# CNC_KONTROL_STM32BIT.net
KiCad netlist of a schematic drawn in EAGLE
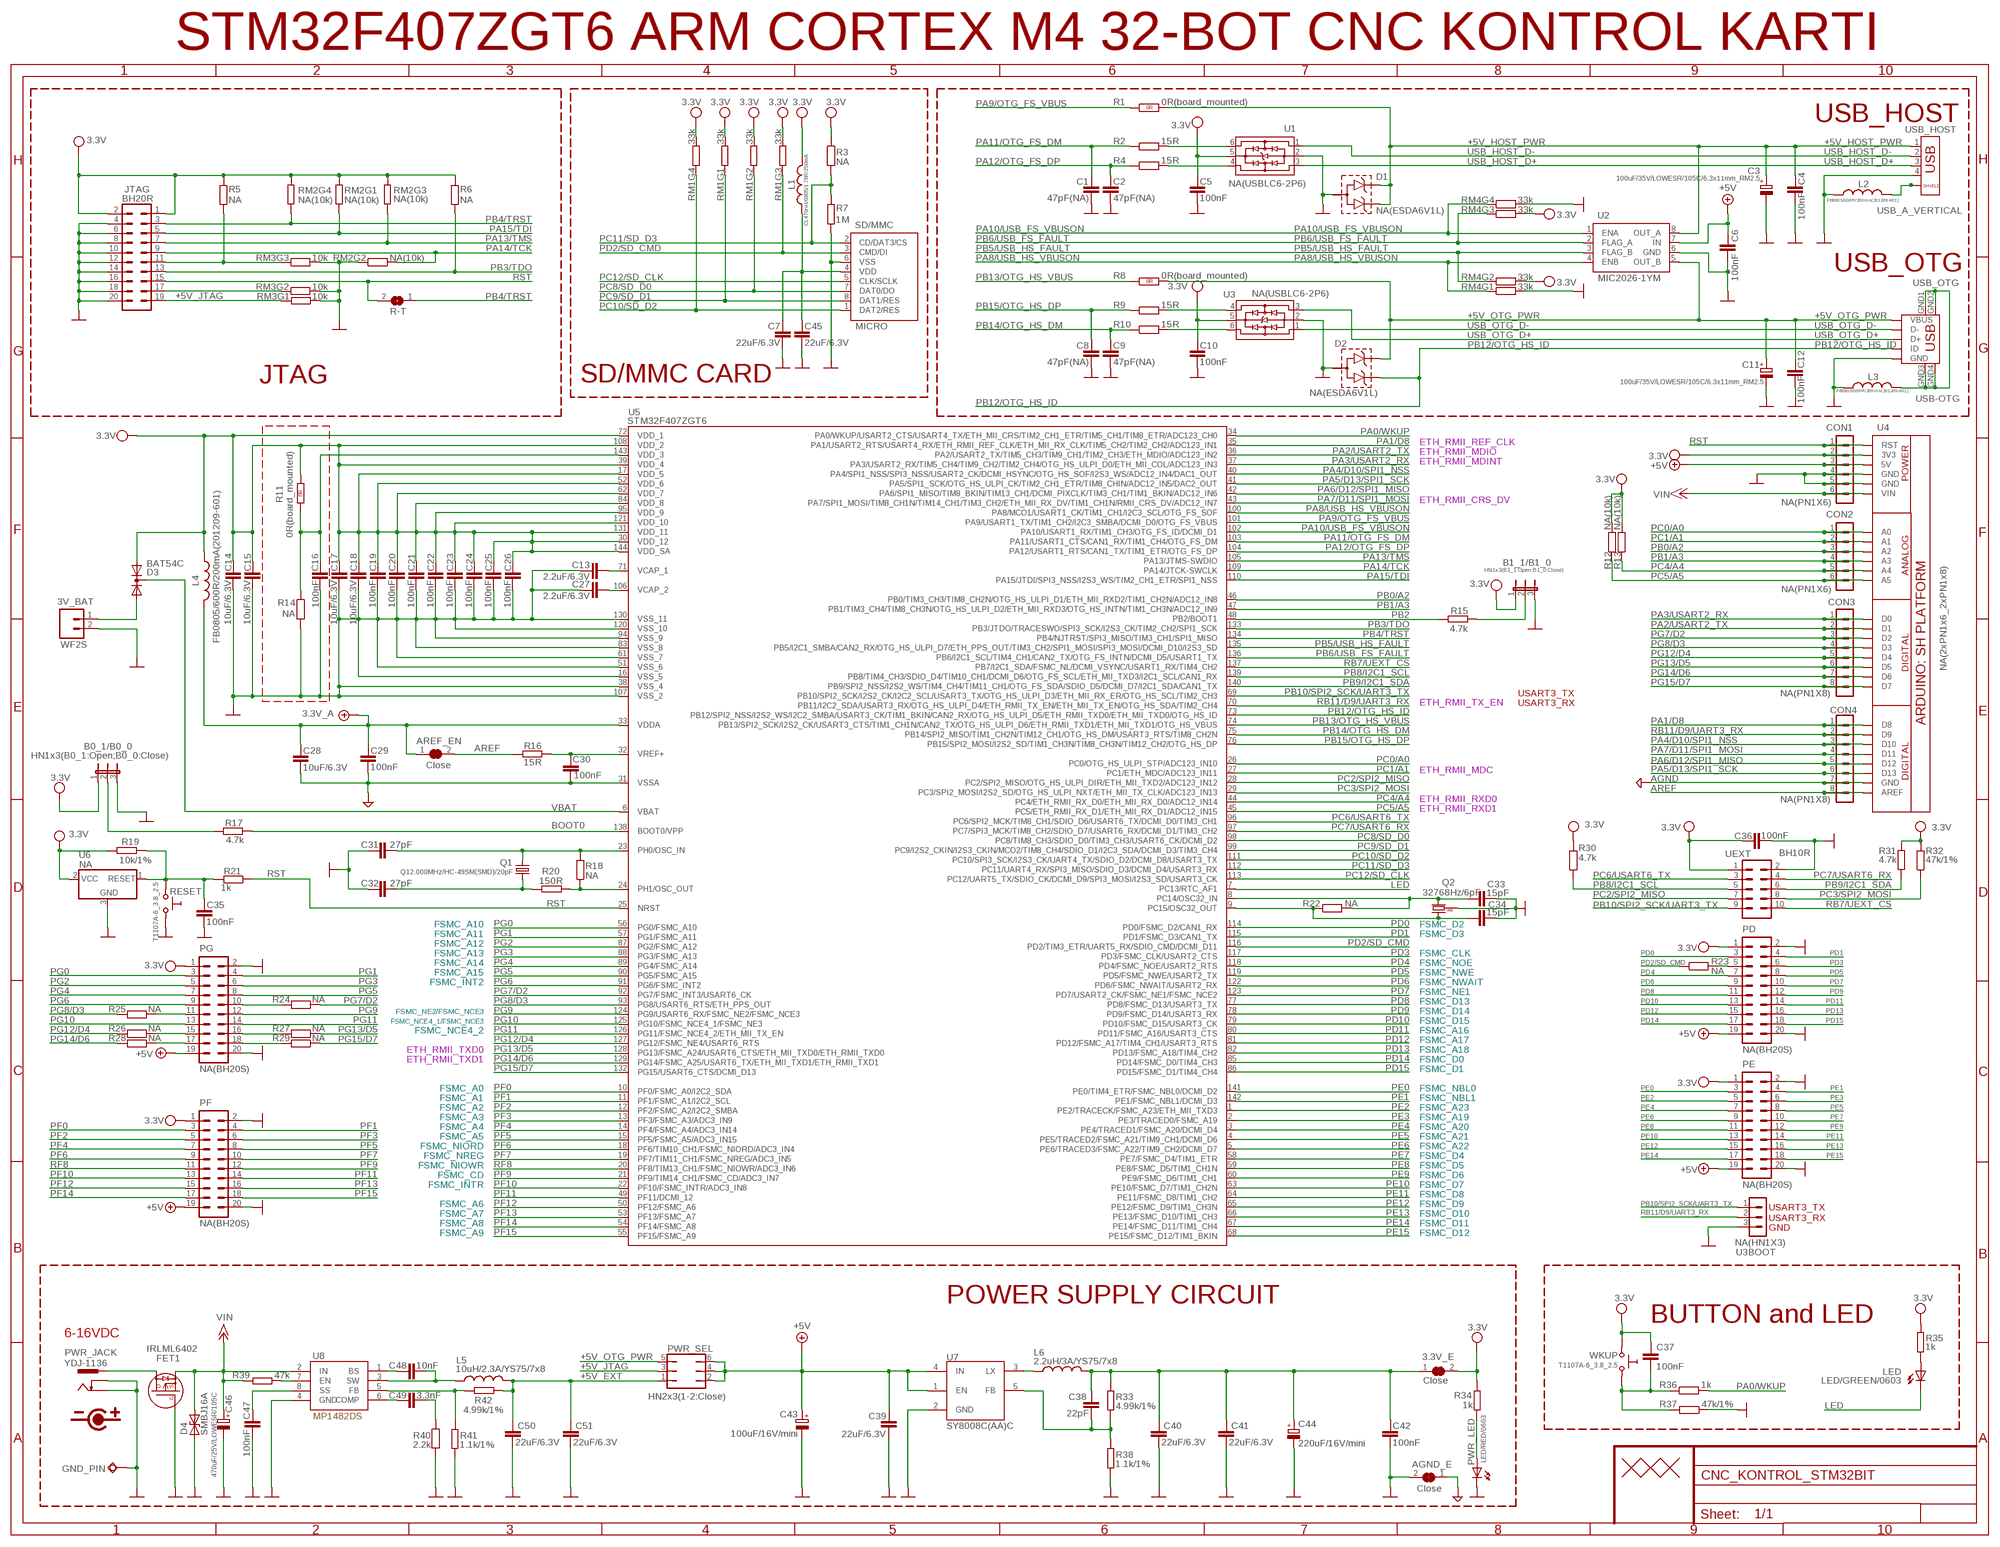
[diagram p0: schematic, sheet 1]

(export (version "E")
  (design (tool "Eeschema 10.0.6"))
  (components
    (comp (ref "3.3V_E")
      (value "Close")
      (footprint "eagle-import:SJ_1_SMALLER_CLOSE")
      (libsource (lib "eagle-import") (part "SJSJ_1_SMALLER_CLOSE"))
    )
    (comp (ref "3V_BAT")
      (value "WF2S")
      (footprint "eagle-import:CON2.54MM-2-0")
      (libsource (lib "eagle-import") (part "CON2PV2-2.54MM"))
    )
    (comp (ref "AGND_E")
      (value "Close")
      (footprint "eagle-import:SJ_1_SMALLER_CLOSE")
      (libsource (lib "eagle-import") (part "SJSJ_1_SMALLER_CLOSE"))
    )
    (comp (ref "AREF_EN")
      (value "Close")
      (footprint "eagle-import:SJ_1_SMALLER_CLOSE")
      (libsource (lib "eagle-import") (part "SJSJ_1_SMALLER_CLOSE"))
    )
    (comp (ref "B0_1/B0_0")
      (value "HN1x3(B0_1:Open;B0_0:Close)")
      (footprint "eagle-import:JP2")
      (libsource (lib "eagle-import") (part "JP2E"))
    )
    (comp (ref "B1_1/B1_0")
      (value "HN1x3(B1_1:Open;B1_0:Close)")
      (footprint "eagle-import:JP2")
      (libsource (lib "eagle-import") (part "JP2E"))
    )
    (comp (ref "C1")
      (value "47pF(NA)")
      (footprint "eagle-import:C0603_DWS")
      (libsource (lib "eagle-import") (part "C-EUC0603_DWS"))
    )
    (comp (ref "C2")
      (value "47pF(NA)")
      (footprint "eagle-import:C0603_DWS")
      (libsource (lib "eagle-import") (part "C-EUC0603_DWS"))
    )
    (comp (ref "C3")
      (value "100uF/35V/LOWESR/105C/6.3x11mm_RM2.5")
      (footprint "eagle-import:E2,5-6,3")
      (libsource (lib "eagle-import") (part "CPOL-EUE2.5-6.3"))
    )
    (comp (ref "C4")
      (value "100nF")
      (footprint "eagle-import:C0603_DWS")
      (libsource (lib "eagle-import") (part "C-EUC0603_DWS"))
    )
    (comp (ref "C5")
      (value "100nF")
      (footprint "eagle-import:C0603_DWS")
      (libsource (lib "eagle-import") (part "C-EUC0603_DWS"))
    )
    (comp (ref "C6")
      (value "100nF")
      (footprint "eagle-import:C0603_DWS")
      (libsource (lib "eagle-import") (part "C-EUC0603_DWS"))
    )
    (comp (ref "C7")
      (value "22uF/6.3V")
      (footprint "eagle-import:C0603_DWS")
      (libsource (lib "eagle-import") (part "C-EUC0603_DWS"))
    )
    (comp (ref "C8")
      (value "47pF(NA)")
      (footprint "eagle-import:C0603_DWS")
      (libsource (lib "eagle-import") (part "C-EUC0603_DWS"))
    )
    (comp (ref "C9")
      (value "47pF(NA)")
      (footprint "eagle-import:C0603_DWS")
      (libsource (lib "eagle-import") (part "C-EUC0603_DWS"))
    )
    (comp (ref "C10")
      (value "100nF")
      (footprint "eagle-import:C0603_DWS")
      (libsource (lib "eagle-import") (part "C-EUC0603_DWS"))
    )
    (comp (ref "C11")
      (value "100uF/35V/LOWESR/105C/6.3x11mm_RM2.5")
      (footprint "eagle-import:E2,5-6,3")
      (libsource (lib "eagle-import") (part "CPOL-EUE2.5-6.3"))
    )
    (comp (ref "C12")
      (value "100nF")
      (footprint "eagle-import:C0603_DWS")
      (libsource (lib "eagle-import") (part "C-EUC0603_DWS"))
    )
    (comp (ref "C13")
      (value "2.2uF/6.3V")
      (footprint "eagle-import:C0603_DWS")
      (libsource (lib "eagle-import") (part "C-EUC0603_DWS"))
    )
    (comp (ref "C14")
      (value "10uF/6.3V")
      (footprint "eagle-import:C0603_DWS")
      (libsource (lib "eagle-import") (part "C-EUC0603_DWS"))
    )
    (comp (ref "C15")
      (value "10uF/6.3V")
      (footprint "eagle-import:C0603_DWS")
      (libsource (lib "eagle-import") (part "C-EUC0603_DWS"))
    )
    (comp (ref "C16")
      (value "100nF")
      (footprint "eagle-import:C0603_DWS")
      (libsource (lib "eagle-import") (part "C-EUC0603_DWS"))
    )
    (comp (ref "C17")
      (value "10uF/6.3V")
      (footprint "eagle-import:C0603_DWS")
      (libsource (lib "eagle-import") (part "C-EUC0603_DWS"))
    )
    (comp (ref "C18")
      (value "10uF/6.3V")
      (footprint "eagle-import:C0603_DWS")
      (libsource (lib "eagle-import") (part "C-EUC0603_DWS"))
    )
    (comp (ref "C19")
      (value "100nF")
      (footprint "eagle-import:C0603_DWS")
      (libsource (lib "eagle-import") (part "C-EUC0603_DWS"))
    )
    (comp (ref "C20")
      (value "100nF")
      (footprint "eagle-import:C0603_DWS")
      (libsource (lib "eagle-import") (part "C-EUC0603_DWS"))
    )
    (comp (ref "C21")
      (value "100nF")
      (footprint "eagle-import:C0603_DWS")
      (libsource (lib "eagle-import") (part "C-EUC0603_DWS"))
    )
    (comp (ref "C22")
      (value "100nF")
      (footprint "eagle-import:C0603_DWS")
      (libsource (lib "eagle-import") (part "C-EUC0603_DWS"))
    )
    (comp (ref "C23")
      (value "100nF")
      (footprint "eagle-import:C0603_DWS")
      (libsource (lib "eagle-import") (part "C-EUC0603_DWS"))
    )
    (comp (ref "C24")
      (value "100nF")
      (footprint "eagle-import:C0603_DWS")
      (libsource (lib "eagle-import") (part "C-EUC0603_DWS"))
    )
    (comp (ref "C25")
      (value "100nF")
      (footprint "eagle-import:C0603_DWS")
      (libsource (lib "eagle-import") (part "C-EUC0603_DWS"))
    )
    (comp (ref "C26")
      (value "100nF")
      (footprint "eagle-import:C0603_DWS")
      (libsource (lib "eagle-import") (part "C-EUC0603_DWS"))
    )
    (comp (ref "C27")
      (value "2.2uF/6.3V")
      (footprint "eagle-import:C0603_DWS")
      (libsource (lib "eagle-import") (part "C-EUC0603_DWS"))
    )
    (comp (ref "C28")
      (value "10uF/6.3V")
      (footprint "eagle-import:C0603_DWS")
      (libsource (lib "eagle-import") (part "C-EUC0603_DWS"))
    )
    (comp (ref "C29")
      (value "100nF")
      (footprint "eagle-import:C0603_DWS")
      (libsource (lib "eagle-import") (part "C-EUC0603_DWS"))
    )
    (comp (ref "C30")
      (value "100nF")
      (footprint "eagle-import:C0603_DWS")
      (libsource (lib "eagle-import") (part "C-EUC0603_DWS"))
    )
    (comp (ref "C31")
      (value "27pF")
      (footprint "eagle-import:C0603_DWS")
      (libsource (lib "eagle-import") (part "C-EUC0603_DWS"))
    )
    (comp (ref "C32")
      (value "27pF")
      (footprint "eagle-import:C0603_DWS")
      (libsource (lib "eagle-import") (part "C-EUC0603_DWS"))
    )
    (comp (ref "C33")
      (value "15pF")
      (footprint "eagle-import:C0603_DWS")
      (libsource (lib "eagle-import") (part "C-EUC0603_DWS"))
    )
    (comp (ref "C34")
      (value "15pF")
      (footprint "eagle-import:C0603_DWS")
      (libsource (lib "eagle-import") (part "C-EUC0603_DWS"))
    )
    (comp (ref "C35")
      (value "100nF")
      (footprint "eagle-import:C0603_DWS")
      (libsource (lib "eagle-import") (part "C-EUC0603_DWS"))
    )
    (comp (ref "C36")
      (value "100nF")
      (footprint "eagle-import:C0603_DWS")
      (libsource (lib "eagle-import") (part "C-EUC0603_DWS"))
    )
    (comp (ref "C37")
      (value "100nF")
      (footprint "eagle-import:C0603_DWS")
      (libsource (lib "eagle-import") (part "C-EUC0603_DWS"))
    )
    (comp (ref "C38")
      (value "22pF")
      (footprint "eagle-import:C0603_DWS")
      (libsource (lib "eagle-import") (part "C-EUC0603_DWS"))
    )
    (comp (ref "C39")
      (value "22uF/6.3V")
      (footprint "eagle-import:C0603_DWS")
      (libsource (lib "eagle-import") (part "C-EUC0603_DWS"))
    )
    (comp (ref "C40")
      (value "22uF/6.3V")
      (footprint "eagle-import:C0603_DWS")
      (libsource (lib "eagle-import") (part "C-EUC0603_DWS"))
    )
    (comp (ref "C41")
      (value "22uF/6.3V")
      (footprint "eagle-import:C0603_DWS")
      (libsource (lib "eagle-import") (part "C-EUC0603_DWS"))
    )
    (comp (ref "C42")
      (value "100nF")
      (footprint "eagle-import:C0603_DWS")
      (libsource (lib "eagle-import") (part "C-EUC0603_DWS"))
    )
    (comp (ref "C43")
      (value "100uF/16V/mini")
      (footprint "eagle-import:E2,5-6")
      (libsource (lib "eagle-import") (part "CPOL-EUE2.5-6"))
    )
    (comp (ref "C44")
      (value "220uF/16V/mini")
      (footprint "eagle-import:E3,5-8")
      (libsource (lib "eagle-import") (part "CPOL-EUE3.5-8"))
    )
    (comp (ref "C45")
      (value "22uF/6.3V")
      (footprint "eagle-import:C0603_DWS")
      (libsource (lib "eagle-import") (part "C-EUC0603_DWS"))
    )
    (comp (ref "C46")
      (value "470uF/25V/LOWESR/105C")
      (footprint "eagle-import:E5-10,5")
      (libsource (lib "eagle-import") (part "CPOL-EUE5-10.5"))
    )
    (comp (ref "C47")
      (value "100nF")
      (footprint "eagle-import:C0603_DWS")
      (libsource (lib "eagle-import") (part "C-EUC0603_DWS"))
    )
    (comp (ref "C48")
      (value "10nF")
      (footprint "eagle-import:C0603_DWS")
      (libsource (lib "eagle-import") (part "C-EUC0603_DWS"))
    )
    (comp (ref "C49")
      (value "3.3nF")
      (footprint "eagle-import:C0603_DWS")
      (libsource (lib "eagle-import") (part "C-EUC0603_DWS"))
    )
    (comp (ref "C50")
      (value "22uF/6.3V")
      (footprint "eagle-import:C0603_DWS")
      (libsource (lib "eagle-import") (part "C-EUC0603_DWS"))
    )
    (comp (ref "C51")
      (value "22uF/6.3V")
      (footprint "eagle-import:C0603_DWS")
      (libsource (lib "eagle-import") (part "C-EUC0603_DWS"))
    )
    (comp (ref "CON1")
      (value "NA(PN1X6)")
      (footprint "eagle-import:PN1X6")
      (libsource (lib "eagle-import") (part "CON6PN1X6"))
    )
    (comp (ref "CON2")
      (value "NA(PN1X6)")
      (footprint "eagle-import:PN1X6")
      (libsource (lib "eagle-import") (part "CON6PN1X6"))
    )
    (comp (ref "CON3")
      (value "NA(PN1X8)")
      (footprint "eagle-import:PN1X8")
      (libsource (lib "eagle-import") (part "CON8PN1X8"))
    )
    (comp (ref "CON4")
      (value "NA(PN1X8)")
      (footprint "eagle-import:PN1X8")
      (libsource (lib "eagle-import") (part "CON8PN1X8"))
    )
    (comp (ref "D1")
      (value "NA(ESDA6V1L)")
      (footprint "eagle-import:SOT-23")
      (libsource (lib "eagle-import") (part "MMBZ5V6ALT1"))
    )
    (comp (ref "D2")
      (value "NA(ESDA6V1L)")
      (footprint "eagle-import:SOT-23")
      (libsource (lib "eagle-import") (part "MMBZ5V6ALT1"))
    )
    (comp (ref "D3")
      (value "BAT54C")
      (footprint "eagle-import:SOT23C")
      (libsource (lib "eagle-import") (part "DIODE_AC-CA_"))
    )
    (comp (ref "D4")
      (value "SMBJ16A")
      (footprint "eagle-import:DO214AA")
      (libsource (lib "eagle-import") (part "SMBJ15A"))
    )
    (comp (ref "FET1")
      (value "IRLML6402")
      (footprint "eagle-import:SOT23")
      (libsource (lib "eagle-import") (part "P-MOS+DIODIRLML6402"))
    )
    (comp (ref "GND_PIN")
      (value "TESTPAD3")
      (footprint "eagle-import:TEST_PAD40_70_SQUARE")
      (libsource (lib "eagle-import") (part "TESTPAD3"))
    )
    (comp (ref "JTAG")
      (value "BH20R")
      (footprint "eagle-import:BH20R")
      (libsource (lib "eagle-import") (part "ML20R"))
    )
    (comp (ref "L1")
      (value "CL470nH/0805/1.76R/250mA")
      (footprint "eagle-import:L0805_5MIL_DWS")
      (libsource (lib "eagle-import") (part "L-USL0805_5MIL_DWS"))
    )
    (comp (ref "L2")
      (value "FB0805/600R/200mA(201209-601)")
      (footprint "eagle-import:L0805_5MIL_DWS")
      (libsource (lib "eagle-import") (part "L-USL0805_5MIL_DWS"))
    )
    (comp (ref "L3")
      (value "FB0805/600R/200mA(201209-601)")
      (footprint "eagle-import:L0805_5MIL_DWS")
      (libsource (lib "eagle-import") (part "L-USL0805_5MIL_DWS"))
    )
    (comp (ref "L4")
      (value "FB0805/600R/200mA(201209-601)")
      (footprint "eagle-import:L0805_5MIL_DWS")
      (libsource (lib "eagle-import") (part "L-USL0805_5MIL_DWS"))
    )
    (comp (ref "L5")
      (value "10uH/2.3A/YS75/7x8")
      (footprint "eagle-import:L7078")
      (libsource (lib "eagle-import") (part "L-USL7078"))
    )
    (comp (ref "L6")
      (value "2.2uH/3A/YS75/7x8")
      (footprint "eagle-import:L7078")
      (libsource (lib "eagle-import") (part "L-USL7078"))
    )
    (comp (ref "LED")
      (value "LED/GREEN/0603")
      (footprint "eagle-import:LED-0603")
      (libsource (lib "eagle-import") (part "LED0603DWS"))
    )
    (comp (ref "PD")
      (value "NA(BH20S)")
      (footprint "eagle-import:ML20-MALE")
      (libsource (lib "eagle-import") (part "ML20"))
    )
    (comp (ref "PE")
      (value "NA(BH20S)")
      (footprint "eagle-import:ML20-MALE")
      (libsource (lib "eagle-import") (part "ML20"))
    )
    (comp (ref "PF")
      (value "NA(BH20S)")
      (footprint "eagle-import:ML20-MALE")
      (libsource (lib "eagle-import") (part "ML20"))
    )
    (comp (ref "PG")
      (value "NA(BH20S)")
      (footprint "eagle-import:ML20-MALE")
      (libsource (lib "eagle-import") (part "ML20"))
    )
    (comp (ref "PWR_JACK")
      (value "YDJ-1136")
      (footprint "eagle-import:PWR_JACK_UNI_MILLING")
      (libsource (lib "eagle-import") (part "PWR-JAKPWR_JACK_UNI_MILLING"))
    )
    (comp (ref "PWR_LED")
      (value "LED/RED/0603")
      (footprint "eagle-import:LED-0603")
      (libsource (lib "eagle-import") (part "LED0603DWS"))
    )
    (comp (ref "PWR_SEL")
      (value "HN2x3(1-2:Close)")
      (footprint "eagle-import:JP3Q_NEW")
      (libsource (lib "eagle-import") (part "JP3QNEW"))
    )
    (comp (ref "Q1")
      (value "Q12.000MHz/HC-49SM(SMD)/20pF")
      (footprint "eagle-import:HC49_SMD2_THIN")
      (libsource (lib "eagle-import") (part "HC49/S1"))
    )
    (comp (ref "Q2")
      (value "32768Hz/6pF")
      (footprint "eagle-import:TC26H_3_REPAIR_SMD")
      (libsource (lib "eagle-import") (part "Q_GND1"))
    )
    (comp (ref "R-T")
      (value "Open")
      (footprint "eagle-import:SJ_1_SMALLER")
      (libsource (lib "eagle-import") (part "SJSJ_SMALLER"))
    )
    (comp (ref "R1")
      (value "0R(board_mounted)")
      (footprint "eagle-import:0603_0R")
      (libsource (lib "eagle-import") (part "R_0R0R(NA)"))
    )
    (comp (ref "R2")
      (value "15R")
      (footprint "eagle-import:R0603_5MIL_DWS")
      (libsource (lib "eagle-import") (part "R-EU_R0603_5MIL_DWS"))
    )
    (comp (ref "R3")
      (value "NA")
      (footprint "eagle-import:R0603_5MIL_DWS_NA")
      (libsource (lib "eagle-import") (part "R-EU_R0603_5MIL_DWS_NA"))
    )
    (comp (ref "R4")
      (value "15R")
      (footprint "eagle-import:R0603_5MIL_DWS")
      (libsource (lib "eagle-import") (part "R-EU_R0603_5MIL_DWS"))
    )
    (comp (ref "R5")
      (value "NA")
      (footprint "eagle-import:R0603_5MIL_DWS_NA")
      (libsource (lib "eagle-import") (part "R-EU_R0603_5MIL_DWS_NA"))
    )
    (comp (ref "R6")
      (value "NA")
      (footprint "eagle-import:R0603_5MIL_DWS_NA")
      (libsource (lib "eagle-import") (part "R-EU_R0603_5MIL_DWS_NA"))
    )
    (comp (ref "R7")
      (value "1M")
      (footprint "eagle-import:R0603_5MIL_DWS")
      (libsource (lib "eagle-import") (part "R-EU_R0603_5MIL_DWS"))
    )
    (comp (ref "R8")
      (value "0R(board_mounted)")
      (footprint "eagle-import:0603_0R")
      (libsource (lib "eagle-import") (part "R_0R0R(NA)"))
    )
    (comp (ref "R9")
      (value "15R")
      (footprint "eagle-import:R0603_5MIL_DWS")
      (libsource (lib "eagle-import") (part "R-EU_R0603_5MIL_DWS"))
    )
    (comp (ref "R10")
      (value "15R")
      (footprint "eagle-import:R0603_5MIL_DWS")
      (libsource (lib "eagle-import") (part "R-EU_R0603_5MIL_DWS"))
    )
    (comp (ref "R11")
      (value "0R(board_mounted)")
      (footprint "eagle-import:0603_0R")
      (libsource (lib "eagle-import") (part "R_0R0R(NA)"))
    )
    (comp (ref "R12")
      (value "NA(10k)")
      (footprint "eagle-import:R0603_5MIL_DWS_NA")
      (libsource (lib "eagle-import") (part "R-EU_R0603_5MIL_DWS_NA"))
    )
    (comp (ref "R13")
      (value "NA(10k)")
      (footprint "eagle-import:R0603_5MIL_DWS_NA")
      (libsource (lib "eagle-import") (part "R-EU_R0603_5MIL_DWS_NA"))
    )
    (comp (ref "R14")
      (value "NA")
      (footprint "eagle-import:R0603_5MIL_DWS_NA")
      (libsource (lib "eagle-import") (part "R-EU_R0603_5MIL_DWS_NA"))
    )
    (comp (ref "R15")
      (value "4.7k")
      (footprint "eagle-import:R0603_5MIL_DWS")
      (libsource (lib "eagle-import") (part "R-EU_R0603_5MIL_DWS"))
    )
    (comp (ref "R16")
      (value "15R")
      (footprint "eagle-import:R0603_5MIL_DWS")
      (libsource (lib "eagle-import") (part "R-EU_R0603_5MIL_DWS"))
    )
    (comp (ref "R17")
      (value "4.7k")
      (footprint "eagle-import:R0603_5MIL_DWS")
      (libsource (lib "eagle-import") (part "R-EU_R0603_5MIL_DWS"))
    )
    (comp (ref "R18")
      (value "NA")
      (footprint "eagle-import:R0603_5MIL_DWS_NA")
      (libsource (lib "eagle-import") (part "R-EU_R0603_5MIL_DWS_NA"))
    )
    (comp (ref "R19")
      (value "10k/1%")
      (footprint "eagle-import:R0603_5MIL_DWS")
      (libsource (lib "eagle-import") (part "R-EU_R0603_5MIL_DWS"))
    )
    (comp (ref "R20")
      (value "150R")
      (footprint "eagle-import:R0603_5MIL_DWS")
      (libsource (lib "eagle-import") (part "R-EU_R0603_5MIL_DWS"))
    )
    (comp (ref "R21")
      (value "1k")
      (footprint "eagle-import:R0603_5MIL_DWS")
      (libsource (lib "eagle-import") (part "R-EU_R0603_5MIL_DWS"))
    )
    (comp (ref "R22")
      (value "NA")
      (footprint "eagle-import:R0603_5MIL_DWS_NA")
      (libsource (lib "eagle-import") (part "R-EU_R0603_5MIL_DWS_NA"))
    )
    (comp (ref "R23")
      (value "NA")
      (footprint "eagle-import:R0603_5MIL_DWS_NA")
      (libsource (lib "eagle-import") (part "R-EU_R0603_5MIL_DWS_NA"))
    )
    (comp (ref "R24")
      (value "NA")
      (footprint "eagle-import:R0603_5MIL_DWS")
      (libsource (lib "eagle-import") (part "R-EU_R0603_5MIL_DWS"))
    )
    (comp (ref "R25")
      (value "NA")
      (footprint "eagle-import:R0603_5MIL_DWS")
      (libsource (lib "eagle-import") (part "R-EU_R0603_5MIL_DWS"))
    )
    (comp (ref "R26")
      (value "NA")
      (footprint "eagle-import:R0603_5MIL_DWS")
      (libsource (lib "eagle-import") (part "R-EU_R0603_5MIL_DWS"))
    )
    (comp (ref "R27")
      (value "NA")
      (footprint "eagle-import:R0603_5MIL_DWS")
      (libsource (lib "eagle-import") (part "R-EU_R0603_5MIL_DWS"))
    )
    (comp (ref "R28")
      (value "NA")
      (footprint "eagle-import:R0603_5MIL_DWS")
      (libsource (lib "eagle-import") (part "R-EU_R0603_5MIL_DWS"))
    )
    (comp (ref "R29")
      (value "NA")
      (footprint "eagle-import:R0603_5MIL_DWS")
      (libsource (lib "eagle-import") (part "R-EU_R0603_5MIL_DWS"))
    )
    (comp (ref "R30")
      (value "4.7k")
      (footprint "eagle-import:R0603_5MIL_DWS")
      (libsource (lib "eagle-import") (part "R-EU_R0603_5MIL_DWS"))
    )
    (comp (ref "R31")
      (value "4.7k")
      (footprint "eagle-import:R0603_5MIL_DWS")
      (libsource (lib "eagle-import") (part "R-EU_R0603_5MIL_DWS"))
    )
    (comp (ref "R32")
      (value "47k/1%")
      (footprint "eagle-import:R0603_5MIL_DWS")
      (libsource (lib "eagle-import") (part "R-EU_R0603_5MIL_DWS"))
    )
    (comp (ref "R33")
      (value "4.99k/1%")
      (footprint "eagle-import:R0603_5MIL_DWS")
      (libsource (lib "eagle-import") (part "R-EU_R0603_5MIL_DWS"))
    )
    (comp (ref "R34")
      (value "1k")
      (footprint "eagle-import:R0603_5MIL_DWS")
      (libsource (lib "eagle-import") (part "R-EU_R0603_5MIL_DWS"))
    )
    (comp (ref "R35")
      (value "1k")
      (footprint "eagle-import:R0603_5MIL_DWS")
      (libsource (lib "eagle-import") (part "R-EU_R0603_5MIL_DWS"))
    )
    (comp (ref "R36")
      (value "1k")
      (footprint "eagle-import:R0603_5MIL_DWS")
      (libsource (lib "eagle-import") (part "R-EU_R0603_5MIL_DWS"))
    )
    (comp (ref "R37")
      (value "47k/1%")
      (footprint "eagle-import:R0603_5MIL_DWS")
      (libsource (lib "eagle-import") (part "R-EU_R0603_5MIL_DWS"))
    )
    (comp (ref "R38")
      (value "1.1k/1%")
      (footprint "eagle-import:R0603_5MIL_DWS")
      (libsource (lib "eagle-import") (part "R-EU_R0603_5MIL_DWS"))
    )
    (comp (ref "R39")
      (value "47k")
      (footprint "eagle-import:R0603_5MIL_DWS")
      (libsource (lib "eagle-import") (part "R-EU_R0603_5MIL_DWS"))
    )
    (comp (ref "R40")
      (value "2.2k")
      (footprint "eagle-import:R0603_5MIL_DWS")
      (libsource (lib "eagle-import") (part "R-EU_R0603_5MIL_DWS"))
    )
    (comp (ref "R41")
      (value "1.1k/1%")
      (footprint "eagle-import:R0603_5MIL_DWS")
      (libsource (lib "eagle-import") (part "R-EU_R0603_5MIL_DWS"))
    )
    (comp (ref "R42")
      (value "4.99k/1%")
      (footprint "eagle-import:R0603_5MIL_DWS")
      (libsource (lib "eagle-import") (part "R-EU_R0603_5MIL_DWS"))
    )
    (comp (ref "RESET")
      (value "T1107A-6_3.8_2.5")
      (footprint "eagle-import:SW-TAKT_6X3.5_SMD")
      (libsource (lib "eagle-import") (part "SW-TAKT6"))
    )
    (comp (ref "RM1")
      (value "33k")
      (footprint "eagle-import:R_MATRIX_4")
      (libsource (lib "eagle-import") (part "R_MATRIX_4E"))
    )
    (comp (ref "RM2")
      (value "NA(10k)")
      (footprint "eagle-import:R_MATRIX_4")
      (libsource (lib "eagle-import") (part "R_MATRIX_4E"))
    )
    (comp (ref "RM3")
      (value "10k")
      (footprint "eagle-import:R_MATRIX_4")
      (libsource (lib "eagle-import") (part "R_MATRIX_4E"))
    )
    (comp (ref "RM4")
      (value "33k")
      (footprint "eagle-import:R_MATRIX_4")
      (libsource (lib "eagle-import") (part "R_MATRIX_4E"))
    )
    (comp (ref "SD/MMC")
      (value "MICRO")
      (footprint "eagle-import:TFR-MEM-CON")
      (libsource (lib "eagle-import") (part "MICRO_SD/MMC"))
    )
    (comp (ref "U$1")
      (value "FIDUCIAL1X2")
      (footprint "eagle-import:FIDUCIAL-1X2")
      (libsource (lib "eagle-import") (part "FIDUCIAL1X2"))
    )
    (comp (ref "U$2")
      (value "FIDUCIAL1X2")
      (footprint "eagle-import:FIDUCIAL-1X2")
      (libsource (lib "eagle-import") (part "FIDUCIAL1X2"))
    )
    (comp (ref "U$9")
      (value "FIDUCIAL1X2")
      (footprint "eagle-import:FIDUCIAL-1X2")
      (libsource (lib "eagle-import") (part "FIDUCIAL1X2"))
    )
    (comp (ref "U1")
      (value "NA(USBLC6-2P6)")
      (footprint "eagle-import:USBLC6-2P6")
      (libsource (lib "eagle-import") (part "USBLC6-2"))
    )
    (comp (ref "U2")
      (value "MIC2026-1YM")
      (footprint "eagle-import:SO-8")
      (libsource (lib "eagle-import") (part "MIC2026-1YM"))
    )
    (comp (ref "U3")
      (value "NA(USBLC6-2P6)")
      (footprint "eagle-import:USBLC6-2P6")
      (libsource (lib "eagle-import") (part "USBLC6-2"))
    )
    (comp (ref "U3BOOT")
      (value "NA(HN1X3)")
      (footprint "eagle-import:HN1X3")
      (libsource (lib "eagle-import") (part "CON3HN1X3"))
    )
    (comp (ref "U4")
      (value "NA(2xPN1x6_2xPN1x8)")
      (footprint "eagle-import:ARDUINO_SHIELD_PLATFORM_WITHOUT_DIMENSION")
      (libsource (lib "eagle-import") (part "ARDUINO_SH_PLATFORM3"))
    )
    (comp (ref "U5")
      (value "STM32F407ZGT6")
      (footprint "eagle-import:LQFP144")
      (libsource (lib "eagle-import") (part "STM32F207ZET6"))
    )
    (comp (ref "U6")
      (value "NA")
      (footprint "eagle-import:SOT23")
      (libsource (lib "eagle-import") (part "RESETMCP130T-300-I/TT"))
    )
    (comp (ref "U7")
      (value "SY8008C(AA)C")
      (footprint "eagle-import:SOT23-5")
      (libsource (lib "eagle-import") (part "SY8008"))
    )
    (comp (ref "U8")
      (value "MP1482DS")
      (footprint "eagle-import:SOIC8")
      (libsource (lib "eagle-import") (part "MP1482"))
    )
    (comp (ref "UEXT")
      (value "BH10R")
      (footprint "eagle-import:BH10R")
      (libsource (lib "eagle-import") (part "ML10R"))
    )
    (comp (ref "USB_HOST")
      (value "USB_A_VERTICAL")
      (footprint "eagle-import:USB_A_VERTICAL_PTH")
      (libsource (lib "eagle-import") (part "USB_SHIELDUSB_A_VERTICAL"))
    )
    (comp (ref "USB_OTG")
      (value "USB-OTG")
      (footprint "eagle-import:USB_MINI_9PIN")
      (libsource (lib "eagle-import") (part "MINI_USB9"))
    )
    (comp (ref "WKUP")
      (value "T1107A-6_3.8_2.5")
      (footprint "eagle-import:SW-TAKT_6X3.5_SMD")
      (libsource (lib "eagle-import") (part "SW-TAKT6"))
    )
  )
  (nets
    (net (code "1") (name "+5V") (class "Default")
      (node (ref "C39") (pin "1") (pinfunction "1_1") (pintype "passive"))
      (node (ref "C43") (pin "+") (pinfunction "+_+") (pintype "passive"))
      (node (ref "C6") (pin "1") (pinfunction "1_1") (pintype "passive"))
      (node (ref "CON1") (pin "3") (pinfunction "3_3") (pintype "passive"))
      (node (ref "PD") (pin "19") (pinfunction "19_19") (pintype "passive"))
      (node (ref "PE") (pin "19") (pinfunction "19_19") (pintype "passive"))
      (node (ref "PF") (pin "19") (pinfunction "19_19") (pintype "passive"))
      (node (ref "PG") (pin "19") (pinfunction "19_19") (pintype "passive"))
      (node (ref "PWR_SEL") (pin "2") (pinfunction "2_2") (pintype "passive"))
      (node (ref "PWR_SEL") (pin "4") (pinfunction "4_4") (pintype "passive"))
      (node (ref "PWR_SEL") (pin "6") (pinfunction "6_6") (pintype "passive"))
      (node (ref "U2") (pin "7") (pinfunction "IN_7") (pintype "input"))
      (node (ref "U4") (pin "5V") (pinfunction "5V_5V") (pintype "bidirectional"))
      (node (ref "U7") (pin "1") (pinfunction "EN_1") (pintype "bidirectional"))
      (node (ref "U7") (pin "4") (pinfunction "IN_4") (pintype "bidirectional"))
    )
    (net (code "2") (name "/+5V_EXT") (class "Default")
      (node (ref "C50") (pin "1") (pinfunction "1_1") (pintype "passive"))
      (node (ref "C51") (pin "1") (pinfunction "1_1") (pintype "passive"))
      (node (ref "L5") (pin "2") (pinfunction "2_2") (pintype "passive"))
      (node (ref "PWR_SEL") (pin "1") (pinfunction "1_1") (pintype "passive"))
      (node (ref "R42") (pin "2") (pinfunction "2_2") (pintype "passive"))
    )
    (net (code "3") (name "/+5V_HOST_PWR") (class "Default")
      (node (ref "C3") (pin "+") (pinfunction "+_+") (pintype "passive"))
      (node (ref "C4") (pin "1") (pinfunction "1_1") (pintype "passive"))
      (node (ref "D1") (pin "1") (pinfunction "1_1") (pintype "passive"))
      (node (ref "D1") (pin "2") (pinfunction "2_2") (pintype "passive"))
      (node (ref "R1") (pin "2") (pinfunction "1.2_2") (pintype "passive"))
      (node (ref "U2") (pin "8") (pinfunction "OUT_A_8") (pintype "output"))
      (node (ref "USB_HOST") (pin "1") (pinfunction "1_1") (pintype "passive"))
    )
    (net (code "4") (name "/+5V_JTAG") (class "Default")
      (node (ref "JTAG") (pin "19") (pinfunction "19_19") (pintype "passive"))
      (node (ref "PWR_SEL") (pin "3") (pinfunction "3_3") (pintype "passive"))
      (node (ref "RM3") (pin "1.1") (pinfunction "1_1.1") (pintype "passive"))
    )
    (net (code "5") (name "/+5V_OTG_PWR") (class "Default")
      (node (ref "C11") (pin "+") (pinfunction "+_+") (pintype "passive"))
      (node (ref "C12") (pin "1") (pinfunction "1_1") (pintype "passive"))
      (node (ref "D2") (pin "1") (pinfunction "1_1") (pintype "passive"))
      (node (ref "PWR_SEL") (pin "5") (pinfunction "5_5") (pintype "passive"))
      (node (ref "R8") (pin "2") (pinfunction "1.2_2") (pintype "passive"))
      (node (ref "U2") (pin "5") (pinfunction "OUT_B_5") (pintype "output"))
      (node (ref "USB_OTG") (pin "VBUS") (pinfunction "VBUS_VBUS") (pintype "power_in"))
    )
    (net (code "6") (name "/AREF") (class "Default")
      (node (ref "AREF_EN") (pin "2") (pinfunction "2_2") (pintype "passive"))
      (node (ref "CON4") (pin "8") (pinfunction "8_8") (pintype "passive"))
      (node (ref "R16") (pin "1") (pinfunction "1_1") (pintype "passive"))
      (node (ref "U4") (pin "AREF") (pinfunction "AREF_AREF") (pintype "bidirectional"))
    )
    (net (code "7") (name "/BOOT0") (class "Default")
      (node (ref "R17") (pin "1") (pinfunction "1_1") (pintype "passive"))
      (node (ref "U5") (pin "138") (pinfunction "BOOT0/VPP_138") (pintype "input"))
    )
    (net (code "8") (name "/LED") (class "Default")
      (node (ref "LED") (pin "C") (pinfunction "C_C") (pintype "passive"))
      (node (ref "U5") (pin "7") (pinfunction "PC13/RTC_AF1_7") (pintype "bidirectional"))
    )
    (net (code "9") (name "/PA0{slash}WKUP") (class "Default")
      (node (ref "R36") (pin "2") (pinfunction "2_2") (pintype "passive"))
      (node (ref "U5") (pin "34") (pinfunction "PA0/WKUP/USART2_CTS/USART4_TX/ETH_MII_CRS/TIM2_CH1_ETR/TIM5_CH1/TIM8_ETR/ADC123_CH0_34") (pintype "bidirectional"))
    )
    (net (code "10") (name "/PA1{slash}D8") (class "Default")
      (node (ref "CON4") (pin "1") (pinfunction "1_1") (pintype "passive"))
      (node (ref "U4") (pin "D8") (pinfunction "D8_D8") (pintype "bidirectional"))
      (node (ref "U5") (pin "35") (pinfunction "PA1/USART2_RTS/USART4_RX/ETH_RMII_REF_CLK/ETH_MII_RX_CLK/TIM5_CH2/TIM2_CH2/ADC123_IN1_35") (pintype "bidirectional"))
    )
    (net (code "11") (name "/PA2{slash}USART2_TX") (class "Default")
      (node (ref "CON3") (pin "2") (pinfunction "2_2") (pintype "passive"))
      (node (ref "U4") (pin "D1") (pinfunction "D1_D1") (pintype "bidirectional"))
      (node (ref "U5") (pin "36") (pinfunction "PA2/USART2_TX/TIM5_CH3/TIM9_CH1/TIM2_CH3/ETH_MDIO/ADC123_IN2_36") (pintype "bidirectional"))
    )
    (net (code "12") (name "/PA3{slash}USART2_RX") (class "Default")
      (node (ref "CON3") (pin "1") (pinfunction "1_1") (pintype "passive"))
      (node (ref "U4") (pin "D0") (pinfunction "D0_D0") (pintype "bidirectional"))
      (node (ref "U5") (pin "37") (pinfunction "PA3/USART2_RX/TIM5_CH4/TIM9_CH2/TIM2_CH4/OTG_HS_ULPI_D0/ETH_MII_COL/ADC123_IN3_37") (pintype "bidirectional"))
    )
    (net (code "13") (name "/PA4{slash}D10{slash}SPI1_NSS") (class "Default")
      (node (ref "CON4") (pin "3") (pinfunction "3_3") (pintype "passive"))
      (node (ref "U4") (pin "D10") (pinfunction "D10_D10") (pintype "bidirectional"))
      (node (ref "U5") (pin "40") (pinfunction "PA4/SPI1_NSS/SPI3_NSS/USART2_CK/DCMI_HSYNC/OTG_HS_SOF/I2S3_WS/ADC12_IN4/DAC1_OUT_40") (pintype "bidirectional"))
    )
    (net (code "14") (name "/PA5{slash}D13{slash}SPI1_SCK") (class "Default")
      (node (ref "CON4") (pin "6") (pinfunction "6_6") (pintype "passive"))
      (node (ref "U4") (pin "D13") (pinfunction "D13_D13") (pintype "bidirectional"))
      (node (ref "U5") (pin "41") (pinfunction "PA5/SPI1_SCK/OTG_HS_ULPI_CK/TIM2_CH1_ETR/TIM8_CHIN/ADC12_IN5/DAC2_OUT_41") (pintype "bidirectional"))
    )
    (net (code "15") (name "/PA6{slash}D12{slash}SPI1_MISO") (class "Default")
      (node (ref "CON4") (pin "5") (pinfunction "5_5") (pintype "passive"))
      (node (ref "U4") (pin "D12") (pinfunction "D12_D12") (pintype "bidirectional"))
      (node (ref "U5") (pin "42") (pinfunction "PA6/SPI1_MISO/TIM8_BKIN/TIM13_CH1/DCMI_PIXCLK/TIM3_CH1/TIM1_BKIN/ADC12_IN6_42") (pintype "bidirectional"))
    )
    (net (code "16") (name "/PA7{slash}D11{slash}SPI1_MOSI") (class "Default")
      (node (ref "CON4") (pin "4") (pinfunction "4_4") (pintype "passive"))
      (node (ref "U4") (pin "D11") (pinfunction "D11_D11") (pintype "bidirectional"))
      (node (ref "U5") (pin "43") (pinfunction "PA7/SPI1_MOSI/TIM8_CH1N/TIM14_CH1/TIM3_CH2/ETH_MII_RX_DV/TIM1_CH1N/RMII_CRS_DV/ADC12_IN7_43") (pintype "bidirectional"))
    )
    (net (code "17") (name "/PA8{slash}USB_HS_VBUSON") (class "Default")
      (node (ref "RM4") (pin "1.1") (pinfunction "1_1.1") (pintype "passive"))
      (node (ref "U2") (pin "4") (pinfunction "ENB_4") (pintype "input"))
      (node (ref "U5") (pin "100") (pinfunction "PA8/MCO1/USART1_CK/TIM1_CH1/I2C3_SCL/OTG_FS_SOF_100") (pintype "bidirectional"))
    )
    (net (code "18") (name "/PA9{slash}OTG_FS_VBUS") (class "Default")
      (node (ref "R1") (pin "1") (pinfunction "1.1_1") (pintype "passive"))
      (node (ref "U5") (pin "101") (pinfunction "PA9/USART1_TX/TIM1_CH2/I2C3_SMBA/DCMI_D0/OTG_FS_VBUS_101") (pintype "bidirectional"))
    )
    (net (code "19") (name "/PA10{slash}USB_FS_VBUSON") (class "Default")
      (node (ref "RM4") (pin "4.1") (pinfunction "1_4.1") (pintype "passive"))
      (node (ref "U2") (pin "1") (pinfunction "ENA_1") (pintype "input"))
      (node (ref "U5") (pin "102") (pinfunction "PA10/USART1_RX/TIM1_CH3/OTG_FS_ID/DCMI_D1_102") (pintype "bidirectional"))
    )
    (net (code "20") (name "/PA11{slash}OTG_FS_DM") (class "Default")
      (node (ref "C1") (pin "1") (pinfunction "1_1") (pintype "passive"))
      (node (ref "R2") (pin "1") (pinfunction "1_1") (pintype "passive"))
      (node (ref "U5") (pin "103") (pinfunction "PA11/USART1_CTS/CAN1_RX/TIM1_CH4/OTG_FS_DM_103") (pintype "bidirectional"))
    )
    (net (code "21") (name "/PA12{slash}OTG_FS_DP") (class "Default")
      (node (ref "C2") (pin "1") (pinfunction "1_1") (pintype "passive"))
      (node (ref "R4") (pin "1") (pinfunction "1_1") (pintype "passive"))
      (node (ref "U5") (pin "104") (pinfunction "PA12/USART1_RTS/CAN1_TX/TIM1_ETR/OTG_FS_DP_104") (pintype "bidirectional"))
    )
    (net (code "22") (name "/PA13{slash}TMS") (class "Default")
      (node (ref "JTAG") (pin "7") (pinfunction "7_7") (pintype "passive"))
      (node (ref "RM2") (pin "3.1") (pinfunction "1_3.1") (pintype "passive"))
      (node (ref "U5") (pin "105") (pinfunction "PA13/JTMS-SWDIO_105") (pintype "bidirectional"))
    )
    (net (code "23") (name "/PA14{slash}TCK") (class "Default")
      (node (ref "JTAG") (pin "9") (pinfunction "9_9") (pintype "passive"))
      (node (ref "RM2") (pin "2.2") (pinfunction "2_2.2") (pintype "passive"))
      (node (ref "U5") (pin "109") (pinfunction "PA14/JTCK-SWCLK_109") (pintype "bidirectional"))
    )
    (net (code "24") (name "/PA15{slash}TDI") (class "Default")
      (node (ref "JTAG") (pin "5") (pinfunction "5_5") (pintype "passive"))
      (node (ref "RM2") (pin "1.1") (pinfunction "1_1.1") (pintype "passive"))
      (node (ref "U5") (pin "110") (pinfunction "PA15/JTDI/SPI3_NSS/I2S3_WS/TIM2_CH1_ETR/SPI1_NSS_110") (pintype "bidirectional"))
    )
    (net (code "25") (name "/PB0{slash}A2") (class "Default")
      (node (ref "CON2") (pin "3") (pinfunction "3_3") (pintype "passive"))
      (node (ref "U4") (pin "A2") (pinfunction "A2_A2") (pintype "bidirectional"))
      (node (ref "U5") (pin "46") (pinfunction "PB0/TIM3_CH3/TIM8_CH2N/OTG_HS_ULPI_D1/ETH_MII_RXD2/TIM1_CH2N/ADC12_IN8_46") (pintype "bidirectional"))
    )
    (net (code "26") (name "/PB1{slash}A3") (class "Default")
      (node (ref "CON2") (pin "4") (pinfunction "4_4") (pintype "passive"))
      (node (ref "U4") (pin "A3") (pinfunction "A3_A3") (pintype "bidirectional"))
      (node (ref "U5") (pin "47") (pinfunction "PB1/TIM3_CH4/TIM8_CH3N/OTG_HS_ULPI_D2/ETH_MII_RXD3/OTG_HS_INTN/TIM1_CH3N/ADC12_IN9_47") (pintype "bidirectional"))
    )
    (net (code "27") (name "/PB2") (class "Default")
      (node (ref "R15") (pin "1") (pinfunction "1_1") (pintype "passive"))
      (node (ref "U5") (pin "48") (pinfunction "PB2/BOOT1_48") (pintype "bidirectional"))
    )
    (net (code "28") (name "/PB3{slash}TDO") (class "Default")
      (node (ref "JTAG") (pin "13") (pinfunction "13_13") (pintype "passive"))
      (node (ref "R6") (pin "1") (pinfunction "1_1") (pintype "passive"))
      (node (ref "U5") (pin "133") (pinfunction "PB3/JTDO/TRACESWO/SPI3_SCK/I2S3_CK/TIM2_CH2/SPI1_SCK_133") (pintype "bidirectional"))
    )
    (net (code "29") (name "/PB4{slash}TRST") (class "Default")
      (node (ref "JTAG") (pin "3") (pinfunction "3_3") (pintype "passive"))
      (node (ref "R-T") (pin "1") (pinfunction "1_1") (pintype "passive"))
      (node (ref "RM2") (pin "4.1") (pinfunction "1_4.1") (pintype "passive"))
      (node (ref "U5") (pin "134") (pinfunction "PB4/NJTRST/SPI3_MISO/TIM3_CH1/SPI1_MISO_134") (pintype "bidirectional"))
    )
    (net (code "30") (name "/PB5{slash}USB_HS_FAULT") (class "Default")
      (node (ref "RM4") (pin "2.1") (pinfunction "1_2.1") (pintype "passive"))
      (node (ref "U2") (pin "3") (pinfunction "FLAG_B_3") (pintype "open_collector"))
      (node (ref "U5") (pin "135") (pinfunction "PB5/I2C1_SMBA/CAN2_RX/OTG_HS_ULPI_D7/ETH_PPS_OUT/TIM3_CH2/SPI1_MOSI/SPI3_MOSI/DCMI_D10/I2S3_SD_135") (pintype "bidirectional"))
    )
    (net (code "31") (name "/PB6{slash}USB_FS_FAULT") (class "Default")
      (node (ref "RM4") (pin "3.1") (pinfunction "1_3.1") (pintype "passive"))
      (node (ref "U2") (pin "2") (pinfunction "FLAG_A_2") (pintype "open_collector"))
      (node (ref "U5") (pin "136") (pinfunction "PB6/I2C1_SCL/TIM4_CH1/CAN2_TX/OTG_FS_INTN/DCMI_D5/USART1_TX_136") (pintype "bidirectional"))
    )
    (net (code "32") (name "/PB8{slash}I2C1_SCL") (class "Default")
      (node (ref "R30") (pin "1") (pinfunction "1_1") (pintype "passive"))
      (node (ref "U5") (pin "139") (pinfunction "PB8/TIM4_CH3/SDIO_D4/TIM10_CH1/DCMI_D6/OTG_FS_SCL/ETH_MII_TXD3/I2C1_SCL/CAN1_RX_139") (pintype "bidirectional"))
      (node (ref "UEXT") (pin "5") (pinfunction "5_5") (pintype "passive"))
    )
    (net (code "33") (name "/PB9{slash}I2C1_SDA") (class "Default")
      (node (ref "R31") (pin "1") (pinfunction "1_1") (pintype "passive"))
      (node (ref "U5") (pin "140") (pinfunction "PB9/SPI2_NSS/I2S2_WS/TIM4_CH4/TIM11_CH1/OTG_FS_SDA/SDIO_D5/DCMI_D7/I2C1_SDA/CAN1_TX_140") (pintype "bidirectional"))
      (node (ref "UEXT") (pin "6") (pinfunction "6_6") (pintype "passive"))
    )
    (net (code "34") (name "/PB10{slash}SPI2_SCK{slash}UART3_TX") (class "Default")
      (node (ref "U3BOOT") (pin "1") (pinfunction "1_1") (pintype "passive"))
      (node (ref "U5") (pin "69") (pinfunction "PB10/SPI2_SCK/I2S2_CK/I2C2_SCL/USART3_TX/OTG_HS_ULPI_D3/ETH_MII_RX_ER/OTG_HS_SCL/TIM2_CH3_69") (pintype "bidirectional"))
      (node (ref "UEXT") (pin "9") (pinfunction "9_9") (pintype "passive"))
    )
    (net (code "35") (name "/PB12{slash}OTG_HS_ID") (class "Default")
      (node (ref "D2") (pin "2") (pinfunction "2_2") (pintype "passive"))
      (node (ref "U5") (pin "73") (pinfunction "PB12/SPI2_NSS/I2S2_WS/I2C2_SMBA/USART3_CK/TIM1_BKIN/CAN2_RX/OTG_HS_ULPI_D5/ETH_RMII_TXD0/ETH_MII_TXD0/OTG_HS_ID_73") (pintype "bidirectional"))
      (node (ref "USB_OTG") (pin "ID") (pinfunction "ID_ID") (pintype "input"))
    )
    (net (code "36") (name "/PB13{slash}OTG_HS_VBUS") (class "Default")
      (node (ref "R8") (pin "1") (pinfunction "1.1_1") (pintype "passive"))
      (node (ref "U5") (pin "74") (pinfunction "PB13/SPI2_SCK/I2S2_CK/USART3_CTS/TIM1_CH1N/CAN2_TX/OTG_HS_ULPI_D6/ETH_RMII_TXD1/ETH_MII_TXD1/OTG_HS_VBUS_74") (pintype "bidirectional"))
    )
    (net (code "37") (name "/PB14{slash}OTG_HS_DM") (class "Default")
      (node (ref "C9") (pin "1") (pinfunction "1_1") (pintype "passive"))
      (node (ref "R10") (pin "1") (pinfunction "1_1") (pintype "passive"))
      (node (ref "U5") (pin "75") (pinfunction "PB14/SPI2_MISO/TIM1_CH2N/TIM12_CH1/OTG_HS_DM/USART3_RTS/TIM8_CH2N_75") (pintype "bidirectional"))
    )
    (net (code "38") (name "/PB15{slash}OTG_HS_DP") (class "Default")
      (node (ref "C8") (pin "1") (pinfunction "1_1") (pintype "passive"))
      (node (ref "R9") (pin "1") (pinfunction "1_1") (pintype "passive"))
      (node (ref "U5") (pin "76") (pinfunction "PB15/SPI2_MOSI/I2S2_SD/TIM1_CH3N/TIM8_CH3N/TIM12_CH2/OTG_HS_DP_76") (pintype "bidirectional"))
    )
    (net (code "39") (name "/PC0{slash}A0") (class "Default")
      (node (ref "CON2") (pin "1") (pinfunction "1_1") (pintype "passive"))
      (node (ref "U4") (pin "A0") (pinfunction "A0_A0") (pintype "bidirectional"))
      (node (ref "U5") (pin "26") (pinfunction "PC0/OTG_HS_ULPI_STP/ADC123_IN10_26") (pintype "bidirectional"))
    )
    (net (code "40") (name "/PC1{slash}A1") (class "Default")
      (node (ref "CON2") (pin "2") (pinfunction "2_2") (pintype "passive"))
      (node (ref "U4") (pin "A1") (pinfunction "A1_A1") (pintype "bidirectional"))
      (node (ref "U5") (pin "27") (pinfunction "PC1/ETH_MDC/ADC123_IN11_27") (pintype "bidirectional"))
    )
    (net (code "41") (name "/PC2{slash}SPI2_MISO") (class "Default")
      (node (ref "U5") (pin "28") (pinfunction "PC2/SPI2_MISO/OTG_HS_ULPI_DIR/ETH_MII_TXD2/ADC123_IN12_28") (pintype "bidirectional"))
      (node (ref "UEXT") (pin "7") (pinfunction "7_7") (pintype "passive"))
    )
    (net (code "42") (name "/PC3{slash}SPI2_MOSI") (class "Default")
      (node (ref "R32") (pin "1") (pinfunction "1_1") (pintype "passive"))
      (node (ref "U5") (pin "29") (pinfunction "PC3/SPI2_MOSI/I2S2_SD/OTG_HS_ULPI_NXT/ETH_MII_TX_CLK/ADC123_IN13_29") (pintype "bidirectional"))
      (node (ref "UEXT") (pin "8") (pinfunction "8_8") (pintype "passive"))
    )
    (net (code "43") (name "/PC4{slash}A4") (class "Default")
      (node (ref "CON2") (pin "5") (pinfunction "5_5") (pintype "passive"))
      (node (ref "R13") (pin "1") (pinfunction "1_1") (pintype "passive"))
      (node (ref "U4") (pin "A4") (pinfunction "A4_A4") (pintype "bidirectional"))
      (node (ref "U5") (pin "44") (pinfunction "PC4/ETH_RMII_RX_D0/ETH_MII_RX_D0/ADC12_IN14_44") (pintype "bidirectional"))
    )
    (net (code "44") (name "/PC5{slash}A5") (class "Default")
      (node (ref "CON2") (pin "6") (pinfunction "6_6") (pintype "passive"))
      (node (ref "R12") (pin "1") (pinfunction "1_1") (pintype "passive"))
      (node (ref "U4") (pin "A5") (pinfunction "A5_A5") (pintype "bidirectional"))
      (node (ref "U5") (pin "45") (pinfunction "PC5/ETH_RMII_RX_D1/ETH_MII_RX_D1/ADC12_IN15_45") (pintype "bidirectional"))
    )
    (net (code "45") (name "/PC6{slash}USART6_TX") (class "Default")
      (node (ref "U5") (pin "96") (pinfunction "PC6/SPI2_MCK/TIM8_CH1/SDIO_D6/USART6_TX/DCMI_D0/TIM3_CH1_96") (pintype "bidirectional"))
      (node (ref "UEXT") (pin "3") (pinfunction "3_3") (pintype "passive"))
    )
    (net (code "46") (name "/PC7{slash}USART6_RX") (class "Default")
      (node (ref "U5") (pin "97") (pinfunction "PC7/SPI3_MCK/TIM8_CH2/SDIO_D7/USART6_RX/DCMI_D1/TIM3_CH2_97") (pintype "bidirectional"))
      (node (ref "UEXT") (pin "4") (pinfunction "4_4") (pintype "passive"))
    )
    (net (code "47") (name "/PC8{slash}SD_D0") (class "Default")
      (node (ref "RM1") (pin "2.1") (pinfunction "1_2.1") (pintype "passive"))
      (node (ref "SD/MMC") (pin "7") (pinfunction "DAT0/DO_7") (pintype "output"))
      (node (ref "U5") (pin "98") (pinfunction "PC8/TIM8_CH3/SDIO_D0/TIM3_CH3/USART6_CK/DCMI_D2_98") (pintype "bidirectional"))
    )
    (net (code "48") (name "/PC9{slash}SD_D1") (class "Default")
      (node (ref "RM1") (pin "1.1") (pinfunction "1_1.1") (pintype "passive"))
      (node (ref "SD/MMC") (pin "8") (pinfunction "DAT1/RES_8") (pintype "bidirectional"))
      (node (ref "U5") (pin "99") (pinfunction "PC9/I2S2_CKIN/I2S3_CKIN/MCO2/TIM8_CH4/SDIO_D1/I2C3_SDA/DCMI_D3/TIM3_CH4_99") (pintype "bidirectional"))
    )
    (net (code "49") (name "/PC10{slash}SD_D2") (class "Default")
      (node (ref "RM1") (pin "4.1") (pinfunction "1_4.1") (pintype "passive"))
      (node (ref "SD/MMC") (pin "1") (pinfunction "DAT2/RES_1") (pintype "bidirectional"))
      (node (ref "U5") (pin "111") (pinfunction "PC10/SPI3_SCK/I2S3_CK/UART4_TX/SDIO_D2/DCMI_D8/USART3_TX_111") (pintype "bidirectional"))
    )
    (net (code "50") (name "/PC11{slash}SD_D3") (class "Default")
      (node (ref "R3") (pin "2") (pinfunction "2_2") (pintype "passive"))
      (node (ref "R7") (pin "1") (pinfunction "1_1") (pintype "passive"))
      (node (ref "SD/MMC") (pin "2") (pinfunction "CD/DAT3/CS_2") (pintype "input"))
      (node (ref "U5") (pin "112") (pinfunction "PC11/UART4_RX/SPI3_MISO/SDIO_D3/DCMI_D4/USART3_RX_112") (pintype "bidirectional"))
    )
    (net (code "51") (name "/PC12{slash}SD_CLK") (class "Default")
      (node (ref "SD/MMC") (pin "5") (pinfunction "CLK/SCLK_5") (pintype "input"))
      (node (ref "U5") (pin "113") (pinfunction "PC12/UART5_TX/SDIO_CK/DCMI_D9/SPI3_MOSI/I2S3_SD/USART3_CK_113") (pintype "bidirectional"))
    )
    (net (code "52") (name "/PD0") (class "Default")
      (node (ref "PD") (pin "3") (pinfunction "3_3") (pintype "passive"))
      (node (ref "U5") (pin "114") (pinfunction "PD0/FSMC_D2/CAN1_RX_114") (pintype "bidirectional"))
    )
    (net (code "53") (name "/PD1") (class "Default")
      (node (ref "PD") (pin "4") (pinfunction "4_4") (pintype "passive"))
      (node (ref "U5") (pin "115") (pinfunction "PD1/FSMC_D3/CAN1_TX_115") (pintype "bidirectional"))
    )
    (net (code "54") (name "/PD2{slash}SD_CMD") (class "Default")
      (node (ref "R23") (pin "1") (pinfunction "1_1") (pintype "passive"))
      (node (ref "RM1") (pin "3.1") (pinfunction "1_3.1") (pintype "passive"))
      (node (ref "SD/MMC") (pin "3") (pinfunction "CMD/DI_3") (pintype "input"))
      (node (ref "U5") (pin "116") (pinfunction "PD2/TIM3_ETR/UART5_RX/SDIO_CMD/DCMI_D11_116") (pintype "bidirectional"))
    )
    (net (code "55") (name "/PD3") (class "Default")
      (node (ref "PD") (pin "6") (pinfunction "6_6") (pintype "passive"))
      (node (ref "U5") (pin "117") (pinfunction "PD3/FSMC_CLK/USART2_CTS_117") (pintype "bidirectional"))
    )
    (net (code "56") (name "/PD4") (class "Default")
      (node (ref "PD") (pin "7") (pinfunction "7_7") (pintype "passive"))
      (node (ref "U5") (pin "118") (pinfunction "PD4/FSMC_NOE/USART2_RTS_118") (pintype "bidirectional"))
    )
    (net (code "57") (name "/PD5") (class "Default")
      (node (ref "PD") (pin "8") (pinfunction "8_8") (pintype "passive"))
      (node (ref "U5") (pin "119") (pinfunction "PD5/FSMC_NWE/USART2_TX_119") (pintype "bidirectional"))
    )
    (net (code "58") (name "/PD6") (class "Default")
      (node (ref "PD") (pin "9") (pinfunction "9_9") (pintype "passive"))
      (node (ref "U5") (pin "122") (pinfunction "PD6/FSMC_NWAIT/USART2_RX_122") (pintype "bidirectional"))
    )
    (net (code "59") (name "/PD7") (class "Default")
      (node (ref "PD") (pin "10") (pinfunction "10_10") (pintype "passive"))
      (node (ref "U5") (pin "123") (pinfunction "PD7/USART2_CK/FSMC_NE1/FSMC_NCE2_123") (pintype "bidirectional"))
    )
    (net (code "60") (name "/PD8") (class "Default")
      (node (ref "PD") (pin "11") (pinfunction "11_11") (pintype "passive"))
      (node (ref "U5") (pin "77") (pinfunction "PD8/FSMC_D13/USART3_TX_77") (pintype "bidirectional"))
    )
    (net (code "61") (name "/PD9") (class "Default")
      (node (ref "PD") (pin "12") (pinfunction "12_12") (pintype "passive"))
      (node (ref "U5") (pin "78") (pinfunction "PD9/FSMC_D14/USART3_RX_78") (pintype "bidirectional"))
    )
    (net (code "62") (name "/PD10") (class "Default")
      (node (ref "PD") (pin "13") (pinfunction "13_13") (pintype "passive"))
      (node (ref "U5") (pin "79") (pinfunction "PD10/FSMC_D15/USART3_CK_79") (pintype "bidirectional"))
    )
    (net (code "63") (name "/PD11") (class "Default")
      (node (ref "PD") (pin "14") (pinfunction "14_14") (pintype "passive"))
      (node (ref "U5") (pin "80") (pinfunction "PD11/FSMC_A16/USART3_CTS_80") (pintype "bidirectional"))
    )
    (net (code "64") (name "/PD12") (class "Default")
      (node (ref "PD") (pin "15") (pinfunction "15_15") (pintype "passive"))
      (node (ref "U5") (pin "81") (pinfunction "PD12/FSMC_A17/TIM4_CH1/USART3_RTS_81") (pintype "bidirectional"))
    )
    (net (code "65") (name "/PD13") (class "Default")
      (node (ref "PD") (pin "16") (pinfunction "16_16") (pintype "passive"))
      (node (ref "U5") (pin "82") (pinfunction "PD13/FSMC_A18/TIM4_CH2_82") (pintype "bidirectional"))
    )
    (net (code "66") (name "/PD14") (class "Default")
      (node (ref "PD") (pin "17") (pinfunction "17_17") (pintype "passive"))
      (node (ref "U5") (pin "85") (pinfunction "PD14/FSMC_D0/TIM4_CH3_85") (pintype "bidirectional"))
    )
    (net (code "67") (name "/PD15") (class "Default")
      (node (ref "PD") (pin "18") (pinfunction "18_18") (pintype "passive"))
      (node (ref "U5") (pin "86") (pinfunction "PD15/FSMC_D1/TIM4_CH4_86") (pintype "bidirectional"))
    )
    (net (code "68") (name "/PE0") (class "Default")
      (node (ref "PE") (pin "3") (pinfunction "3_3") (pintype "passive"))
      (node (ref "U5") (pin "141") (pinfunction "PE0/TIM4_ETR/FSMC_NBL0/DCMI_D2_141") (pintype "bidirectional"))
    )
    (net (code "69") (name "/PE1") (class "Default")
      (node (ref "PE") (pin "4") (pinfunction "4_4") (pintype "passive"))
      (node (ref "U5") (pin "142") (pinfunction "PE1/FSMC_NBL1/DCMI_D3_142") (pintype "bidirectional"))
    )
    (net (code "70") (name "/PE2") (class "Default")
      (node (ref "PE") (pin "5") (pinfunction "5_5") (pintype "passive"))
      (node (ref "U5") (pin "1") (pinfunction "PE2/TRACECK/FSMC_A23/ETH_MII_TXD3_1") (pintype "bidirectional"))
    )
    (net (code "71") (name "/PE3") (class "Default")
      (node (ref "PE") (pin "6") (pinfunction "6_6") (pintype "passive"))
      (node (ref "U5") (pin "2") (pinfunction "PE3/TRACED0/FSMC_A19_2") (pintype "bidirectional"))
    )
    (net (code "72") (name "/PE4") (class "Default")
      (node (ref "PE") (pin "7") (pinfunction "7_7") (pintype "passive"))
      (node (ref "U5") (pin "3") (pinfunction "PE4/TRACED1/FSMC_A20/DCMI_D4_3") (pintype "bidirectional"))
    )
    (net (code "73") (name "/PE5") (class "Default")
      (node (ref "PE") (pin "8") (pinfunction "8_8") (pintype "passive"))
      (node (ref "U5") (pin "4") (pinfunction "PE5/TRACED2/FSMC_A21/TIM9_CH1/DCMI_D6_4") (pintype "bidirectional"))
    )
    (net (code "74") (name "/PE6") (class "Default")
      (node (ref "PE") (pin "9") (pinfunction "9_9") (pintype "passive"))
      (node (ref "U5") (pin "5") (pinfunction "PE6/TRACED3/FSMC_A22/TIM9_CH2/DCMI_D7_5") (pintype "bidirectional"))
    )
    (net (code "75") (name "/PE7") (class "Default")
      (node (ref "PE") (pin "10") (pinfunction "10_10") (pintype "passive"))
      (node (ref "U5") (pin "58") (pinfunction "PE7/FSMC_D4/TIM1_ETR_58") (pintype "bidirectional"))
    )
    (net (code "76") (name "/PE8") (class "Default")
      (node (ref "PE") (pin "11") (pinfunction "11_11") (pintype "passive"))
      (node (ref "U5") (pin "59") (pinfunction "PE8/FSMC_D5/TIM1_CH1N_59") (pintype "bidirectional"))
    )
    (net (code "77") (name "/PE9") (class "Default")
      (node (ref "PE") (pin "12") (pinfunction "12_12") (pintype "passive"))
      (node (ref "U5") (pin "60") (pinfunction "PE9/FSMC_D6/TIM1_CH1_60") (pintype "bidirectional"))
    )
    (net (code "78") (name "/PE10") (class "Default")
      (node (ref "PE") (pin "13") (pinfunction "13_13") (pintype "passive"))
      (node (ref "U5") (pin "63") (pinfunction "PE10/FSMC_D7/TIM1_CH2N_63") (pintype "bidirectional"))
    )
    (net (code "79") (name "/PE11") (class "Default")
      (node (ref "PE") (pin "14") (pinfunction "14_14") (pintype "passive"))
      (node (ref "U5") (pin "64") (pinfunction "PE11/FSMC_D8/TIM1_CH2_64") (pintype "bidirectional"))
    )
    (net (code "80") (name "/PE12") (class "Default")
      (node (ref "PE") (pin "15") (pinfunction "15_15") (pintype "passive"))
      (node (ref "U5") (pin "65") (pinfunction "PE12/FSMC_D9/TIM1_CH3N_65") (pintype "bidirectional"))
    )
    (net (code "81") (name "/PE13") (class "Default")
      (node (ref "PE") (pin "16") (pinfunction "16_16") (pintype "passive"))
      (node (ref "U5") (pin "66") (pinfunction "PE13/FSMC_D10/TIM1_CH3_66") (pintype "bidirectional"))
    )
    (net (code "82") (name "/PE14") (class "Default")
      (node (ref "PE") (pin "17") (pinfunction "17_17") (pintype "passive"))
      (node (ref "U5") (pin "67") (pinfunction "PE14/FSMC_D11/TIM1_CH4_67") (pintype "bidirectional"))
    )
    (net (code "83") (name "/PE15") (class "Default")
      (node (ref "PE") (pin "18") (pinfunction "18_18") (pintype "passive"))
      (node (ref "U5") (pin "68") (pinfunction "PE15/FSMC_D12/TIM1_BKIN_68") (pintype "bidirectional"))
    )
    (net (code "84") (name "/PF0") (class "Default")
      (node (ref "PF") (pin "3") (pinfunction "3_3") (pintype "passive"))
      (node (ref "U5") (pin "10") (pinfunction "PF0/FSMC_A0/I2C2_SDA_10") (pintype "bidirectional"))
    )
    (net (code "85") (name "/PF1") (class "Default")
      (node (ref "PF") (pin "4") (pinfunction "4_4") (pintype "passive"))
      (node (ref "U5") (pin "11") (pinfunction "PF1/FSMC_A1/I2C2_SCL_11") (pintype "bidirectional"))
    )
    (net (code "86") (name "/PF2") (class "Default")
      (node (ref "PF") (pin "5") (pinfunction "5_5") (pintype "passive"))
      (node (ref "U5") (pin "12") (pinfunction "PF2/FSMC_A2/I2C2_SMBA_12") (pintype "bidirectional"))
    )
    (net (code "87") (name "/PF3") (class "Default")
      (node (ref "PF") (pin "6") (pinfunction "6_6") (pintype "passive"))
      (node (ref "U5") (pin "13") (pinfunction "PF3/FSMC_A3/ADC3_IN9_13") (pintype "bidirectional"))
    )
    (net (code "88") (name "/PF4") (class "Default")
      (node (ref "PF") (pin "7") (pinfunction "7_7") (pintype "passive"))
      (node (ref "U5") (pin "14") (pinfunction "PF4/FSMC_A4/ADC3_IN14_14") (pintype "bidirectional"))
    )
    (net (code "89") (name "/PF5") (class "Default")
      (node (ref "PF") (pin "8") (pinfunction "8_8") (pintype "passive"))
      (node (ref "U5") (pin "15") (pinfunction "PF5/FSMC_A5/ADC3_IN15_15") (pintype "bidirectional"))
    )
    (net (code "90") (name "/PF6") (class "Default")
      (node (ref "PF") (pin "9") (pinfunction "9_9") (pintype "passive"))
      (node (ref "U5") (pin "18") (pinfunction "PF6/TIM10_CH1/FSMC_NIORD/ADC3_IN4_18") (pintype "bidirectional"))
    )
    (net (code "91") (name "/PF7") (class "Default")
      (node (ref "PF") (pin "10") (pinfunction "10_10") (pintype "passive"))
      (node (ref "U5") (pin "19") (pinfunction "PF7/TIM11_CH1/FSMC_NREG/ADC3_IN5_19") (pintype "bidirectional"))
    )
    (net (code "92") (name "/PF9") (class "Default")
      (node (ref "PF") (pin "12") (pinfunction "12_12") (pintype "passive"))
      (node (ref "U5") (pin "21") (pinfunction "PF9/TIM14_CH1/FSMC_CD/ADC3_IN7_21") (pintype "bidirectional"))
    )
    (net (code "93") (name "/PF10") (class "Default")
      (node (ref "PF") (pin "13") (pinfunction "13_13") (pintype "passive"))
      (node (ref "U5") (pin "22") (pinfunction "PF10/FSMC_INTR/ADC3_IN8_22") (pintype "bidirectional"))
    )
    (net (code "94") (name "/PF11") (class "Default")
      (node (ref "PF") (pin "14") (pinfunction "14_14") (pintype "passive"))
      (node (ref "U5") (pin "49") (pinfunction "PF11/DCMI_12_49") (pintype "bidirectional"))
    )
    (net (code "95") (name "/PF12") (class "Default")
      (node (ref "PF") (pin "15") (pinfunction "15_15") (pintype "passive"))
      (node (ref "U5") (pin "50") (pinfunction "PF12/FSMC_A6_50") (pintype "bidirectional"))
    )
    (net (code "96") (name "/PF13") (class "Default")
      (node (ref "PF") (pin "16") (pinfunction "16_16") (pintype "passive"))
      (node (ref "U5") (pin "53") (pinfunction "PF13/FSMC_A7_53") (pintype "bidirectional"))
    )
    (net (code "97") (name "/PF14") (class "Default")
      (node (ref "PF") (pin "17") (pinfunction "17_17") (pintype "passive"))
      (node (ref "U5") (pin "54") (pinfunction "PF14/FSMC_A8_54") (pintype "bidirectional"))
    )
    (net (code "98") (name "/PF15") (class "Default")
      (node (ref "PF") (pin "18") (pinfunction "18_18") (pintype "passive"))
      (node (ref "U5") (pin "55") (pinfunction "PF15/FSMC_A9_55") (pintype "bidirectional"))
    )
    (net (code "99") (name "/PG0") (class "Default")
      (node (ref "PG") (pin "3") (pinfunction "3_3") (pintype "passive"))
      (node (ref "U5") (pin "56") (pinfunction "PG0/FSMC_A10_56") (pintype "bidirectional"))
    )
    (net (code "100") (name "/PG1") (class "Default")
      (node (ref "PG") (pin "4") (pinfunction "4_4") (pintype "passive"))
      (node (ref "U5") (pin "57") (pinfunction "PG1/FSMC_A11_57") (pintype "bidirectional"))
    )
    (net (code "101") (name "/PG2") (class "Default")
      (node (ref "PG") (pin "5") (pinfunction "5_5") (pintype "passive"))
      (node (ref "U5") (pin "87") (pinfunction "PG2/FSMC_A12_87") (pintype "bidirectional"))
    )
    (net (code "102") (name "/PG3") (class "Default")
      (node (ref "PG") (pin "6") (pinfunction "6_6") (pintype "passive"))
      (node (ref "U5") (pin "88") (pinfunction "PG3/FSMC_A13_88") (pintype "bidirectional"))
    )
    (net (code "103") (name "/PG4") (class "Default")
      (node (ref "PG") (pin "7") (pinfunction "7_7") (pintype "passive"))
      (node (ref "U5") (pin "89") (pinfunction "PG4/FSMC_A14_89") (pintype "bidirectional"))
    )
    (net (code "104") (name "/PG5") (class "Default")
      (node (ref "PG") (pin "8") (pinfunction "8_8") (pintype "passive"))
      (node (ref "U5") (pin "90") (pinfunction "PG5/FSMC_A15_90") (pintype "bidirectional"))
    )
    (net (code "105") (name "/PG6") (class "Default")
      (node (ref "PG") (pin "9") (pinfunction "9_9") (pintype "passive"))
      (node (ref "U5") (pin "91") (pinfunction "PG6/FSMC_INT2_91") (pintype "bidirectional"))
    )
    (net (code "106") (name "/PG7{slash}D2") (class "Default")
      (node (ref "CON3") (pin "3") (pinfunction "3_3") (pintype "passive"))
      (node (ref "R24") (pin "1") (pinfunction "1_1") (pintype "passive"))
      (node (ref "U4") (pin "D2") (pinfunction "D2_D2") (pintype "bidirectional"))
      (node (ref "U5") (pin "92") (pinfunction "PG7/FSMC_INT3/USART6_CK_92") (pintype "bidirectional"))
    )
    (net (code "107") (name "/PG8{slash}D3") (class "Default")
      (node (ref "CON3") (pin "4") (pinfunction "4_4") (pintype "passive"))
      (node (ref "R25") (pin "2") (pinfunction "2_2") (pintype "passive"))
      (node (ref "U4") (pin "D3") (pinfunction "D3_D3") (pintype "bidirectional"))
      (node (ref "U5") (pin "93") (pinfunction "PG8/USART6_RTS/ETH_PPS_OUT_93") (pintype "bidirectional"))
    )
    (net (code "108") (name "/PG9") (class "Default")
      (node (ref "PG") (pin "12") (pinfunction "12_12") (pintype "passive"))
      (node (ref "U5") (pin "124") (pinfunction "PG9/USART6_RX/FSMC_NE2/FSMC_NCE3_124") (pintype "bidirectional"))
    )
    (net (code "109") (name "/PG10") (class "Default")
      (node (ref "PG") (pin "13") (pinfunction "13_13") (pintype "passive"))
      (node (ref "U5") (pin "125") (pinfunction "PG10/FSMC_NCE4_1/FSMC_NE3_125") (pintype "bidirectional"))
    )
    (net (code "110") (name "/PG11") (class "Default")
      (node (ref "PG") (pin "14") (pinfunction "14_14") (pintype "passive"))
      (node (ref "U5") (pin "126") (pinfunction "PG11/FSMC_NCE4_2/ETH_MII_TX_EN_126") (pintype "bidirectional"))
    )
    (net (code "111") (name "/PG12{slash}D4") (class "Default")
      (node (ref "CON3") (pin "5") (pinfunction "5_5") (pintype "passive"))
      (node (ref "R26") (pin "2") (pinfunction "2_2") (pintype "passive"))
      (node (ref "U4") (pin "D4") (pinfunction "D4_D4") (pintype "bidirectional"))
      (node (ref "U5") (pin "127") (pinfunction "PG12/FSMC_NE4/USART6_RTS_127") (pintype "bidirectional"))
    )
    (net (code "112") (name "/PG13{slash}D5") (class "Default")
      (node (ref "CON3") (pin "6") (pinfunction "6_6") (pintype "passive"))
      (node (ref "R27") (pin "1") (pinfunction "1_1") (pintype "passive"))
      (node (ref "U4") (pin "D5") (pinfunction "D5_D5") (pintype "bidirectional"))
      (node (ref "U5") (pin "128") (pinfunction "PG13/FSMC_A24/USART6_CTS/ETH_MII_TXD0/ETH_RMII_TXD0_128") (pintype "bidirectional"))
    )
    (net (code "113") (name "/PG14{slash}D6") (class "Default")
      (node (ref "CON3") (pin "7") (pinfunction "7_7") (pintype "passive"))
      (node (ref "R28") (pin "2") (pinfunction "2_2") (pintype "passive"))
      (node (ref "U4") (pin "D6") (pinfunction "D6_D6") (pintype "bidirectional"))
      (node (ref "U5") (pin "129") (pinfunction "PG14/FSMC_A25/USART6_TX/ETH_MII_TXD1/ETH_RMII_TXD1_129") (pintype "bidirectional"))
    )
    (net (code "114") (name "/PG15{slash}D7") (class "Default")
      (node (ref "CON3") (pin "8") (pinfunction "8_8") (pintype "passive"))
      (node (ref "R29") (pin "1") (pinfunction "1_1") (pintype "passive"))
      (node (ref "U4") (pin "D7") (pinfunction "D7_D7") (pintype "bidirectional"))
      (node (ref "U5") (pin "132") (pinfunction "PG15/USART6_CTS/DCMI_D13_132") (pintype "bidirectional"))
    )
    (net (code "115") (name "/RB7{slash}UEXT_CS") (class "Default")
      (node (ref "U5") (pin "137") (pinfunction "PB7/I2C1_SDA/FSMC_NL/DCMI_VSYNC/USART1_RX/TIM4_CH2_137") (pintype "bidirectional"))
      (node (ref "UEXT") (pin "10") (pinfunction "10_10") (pintype "passive"))
    )
    (net (code "116") (name "/RB11{slash}D9{slash}UART3_RX") (class "Default")
      (node (ref "CON4") (pin "2") (pinfunction "2_2") (pintype "passive"))
      (node (ref "U3BOOT") (pin "2") (pinfunction "2_2") (pintype "passive"))
      (node (ref "U4") (pin "D9") (pinfunction "D9_D9") (pintype "bidirectional"))
      (node (ref "U5") (pin "70") (pinfunction "PB11/I2C2_SDA/USART3_RX/OTG_HS_ULPI_D4/ETH_RMII_TX_EN/ETH_MII_TX_EN/OTG_HS_SDA/TIM2_CH4_70") (pintype "bidirectional"))
    )
    (net (code "117") (name "/RF8") (class "Default")
      (node (ref "PF") (pin "11") (pinfunction "11_11") (pintype "passive"))
      (node (ref "U5") (pin "20") (pinfunction "PF8/TIM13_CH1/FSMC_NIOWR/ADC3_IN6_20") (pintype "bidirectional"))
    )
    (net (code "118") (name "/RST") (class "Default")
      (node (ref "CON1") (pin "1") (pinfunction "1_1") (pintype "passive"))
      (node (ref "JTAG") (pin "15") (pinfunction "15_15") (pintype "passive"))
      (node (ref "R-T") (pin "2") (pinfunction "2_2") (pintype "passive"))
      (node (ref "R21") (pin "1") (pinfunction "1_1") (pintype "passive"))
      (node (ref "U4") (pin "RST") (pinfunction "RST_RST") (pintype "bidirectional"))
      (node (ref "U5") (pin "25") (pinfunction "NRST_25") (pintype "power_in"))
    )
    (net (code "119") (name "/USB_HOST_D+") (class "Default")
      (node (ref "U1") (pin "3") (pinfunction "3_3") (pintype "bidirectional"))
      (node (ref "USB_HOST") (pin "3") (pinfunction "3_3") (pintype "passive"))
    )
    (net (code "120") (name "/USB_HOST_D-") (class "Default")
      (node (ref "U1") (pin "1") (pinfunction "1_1") (pintype "bidirectional"))
      (node (ref "USB_HOST") (pin "2") (pinfunction "2_2") (pintype "passive"))
    )
    (net (code "121") (name "/USB_OTG_D+") (class "Default")
      (node (ref "U3") (pin "3") (pinfunction "3_3") (pintype "bidirectional"))
      (node (ref "USB_OTG") (pin "D+") (pinfunction "D+_D+") (pintype "input"))
    )
    (net (code "122") (name "/USB_OTG_D-") (class "Default")
      (node (ref "U3") (pin "1") (pinfunction "1_1") (pintype "bidirectional"))
      (node (ref "USB_OTG") (pin "D-") (pinfunction "D-_D-") (pintype "input"))
    )
    (net (code "123") (name "/VBAT") (class "Default")
      (node (ref "D3") (pin "3") (pinfunction "K_3") (pintype "passive"))
      (node (ref "U5") (pin "6") (pinfunction "VBAT_6") (pintype "power_in"))
    )
    (net (code "124") (name "3.3V") (class "Default")
      (node (ref "3.3V_E") (pin "2") (pinfunction "2_2") (pintype "passive"))
      (node (ref "B0_1/B0_0") (pin "1") (pinfunction "1_1") (pintype "passive"))
      (node (ref "B1_1/B1_0") (pin "1") (pinfunction "1_1") (pintype "passive"))
      (node (ref "C10") (pin "2") (pinfunction "2_2") (pintype "passive"))
      (node (ref "C14") (pin "2") (pinfunction "2_2") (pintype "passive"))
      (node (ref "C15") (pin "2") (pinfunction "2_2") (pintype "passive"))
      (node (ref "C17") (pin "2") (pinfunction "2_2") (pintype "passive"))
      (node (ref "C18") (pin "2") (pinfunction "2_2") (pintype "passive"))
      (node (ref "C19") (pin "2") (pinfunction "2_2") (pintype "passive"))
      (node (ref "C20") (pin "2") (pinfunction "2_2") (pintype "passive"))
      (node (ref "C21") (pin "2") (pinfunction "2_2") (pintype "passive"))
      (node (ref "C22") (pin "2") (pinfunction "2_2") (pintype "passive"))
      (node (ref "C23") (pin "2") (pinfunction "2_2") (pintype "passive"))
      (node (ref "C24") (pin "2") (pinfunction "2_2") (pintype "passive"))
      (node (ref "C25") (pin "2") (pinfunction "2_2") (pintype "passive"))
      (node (ref "C26") (pin "2") (pinfunction "2_2") (pintype "passive"))
      (node (ref "C36") (pin "2") (pinfunction "2_2") (pintype "passive"))
      (node (ref "C37") (pin "2") (pinfunction "2_2") (pintype "passive"))
      (node (ref "C5") (pin "2") (pinfunction "2_2") (pintype "passive"))
      (node (ref "CON1") (pin "2") (pinfunction "2_2") (pintype "passive"))
      (node (ref "D3") (pin "1") (pinfunction "A1_1") (pintype "passive"))
      (node (ref "JTAG") (pin "1") (pinfunction "1_1") (pintype "passive"))
      (node (ref "JTAG") (pin "2") (pinfunction "2_2") (pintype "passive"))
      (node (ref "L1") (pin "1") (pinfunction "1_1") (pintype "passive"))
      (node (ref "L4") (pin "1") (pinfunction "1_1") (pintype "passive"))
      (node (ref "PD") (pin "1") (pinfunction "1_1") (pintype "passive"))
      (node (ref "PE") (pin "1") (pinfunction "1_1") (pintype "passive"))
      (node (ref "PF") (pin "1") (pinfunction "1_1") (pintype "passive"))
      (node (ref "PG") (pin "1") (pinfunction "1_1") (pintype "passive"))
      (node (ref "R11") (pin "2") (pinfunction "1.2_2") (pintype "passive"))
      (node (ref "R12") (pin "2") (pinfunction "2_2") (pintype "passive"))
      (node (ref "R13") (pin "2") (pinfunction "2_2") (pintype "passive"))
      (node (ref "R19") (pin "2") (pinfunction "2_2") (pintype "passive"))
      (node (ref "R3") (pin "1") (pinfunction "1_1") (pintype "passive"))
      (node (ref "R30") (pin "2") (pinfunction "2_2") (pintype "passive"))
      (node (ref "R31") (pin "2") (pinfunction "2_2") (pintype "passive"))
      (node (ref "R32") (pin "2") (pinfunction "2_2") (pintype "passive"))
      (node (ref "R34") (pin "1") (pinfunction "1_1") (pintype "passive"))
      (node (ref "R35") (pin "2") (pinfunction "2_2") (pintype "passive"))
      (node (ref "R5") (pin "2") (pinfunction "2_2") (pintype "passive"))
      (node (ref "R6") (pin "2") (pinfunction "2_2") (pintype "passive"))
      (node (ref "RM1") (pin "1.2") (pinfunction "2_1.2") (pintype "passive"))
      (node (ref "RM1") (pin "2.2") (pinfunction "2_2.2") (pintype "passive"))
      (node (ref "RM1") (pin "3.2") (pinfunction "2_3.2") (pintype "passive"))
      (node (ref "RM1") (pin "4.2") (pinfunction "2_4.2") (pintype "passive"))
      (node (ref "RM2") (pin "1.2") (pinfunction "2_1.2") (pintype "passive"))
      (node (ref "RM2") (pin "3.2") (pinfunction "2_3.2") (pintype "passive"))
      (node (ref "RM2") (pin "4.2") (pinfunction "2_4.2") (pintype "passive"))
      (node (ref "RM4") (pin "2.2") (pinfunction "2_2.2") (pintype "passive"))
      (node (ref "RM4") (pin "3.2") (pinfunction "2_3.2") (pintype "passive"))
      (node (ref "U1") (pin "5") (pinfunction "5_5") (pintype "power_in"))
      (node (ref "U3") (pin "5") (pinfunction "5_5") (pintype "power_in"))
      (node (ref "U4") (pin "3V3") (pinfunction "3V3_3V3") (pintype "bidirectional"))
      (node (ref "U5") (pin "108") (pinfunction "VDD_2_108") (pintype "power_in"))
      (node (ref "U5") (pin "121") (pinfunction "VDD_10_121") (pintype "power_in"))
      (node (ref "U5") (pin "131") (pinfunction "VDD_11_131") (pintype "power_in"))
      (node (ref "U5") (pin "144") (pinfunction "VDD_SA_144") (pintype "power_in"))
      (node (ref "U5") (pin "17") (pinfunction "VDD_5_17") (pintype "power_in"))
      (node (ref "U5") (pin "30") (pinfunction "VDD_12_30") (pintype "power_in"))
      (node (ref "U5") (pin "39") (pinfunction "VDD_4_39") (pintype "power_in"))
      (node (ref "U5") (pin "52") (pinfunction "VDD_6_52") (pintype "power_in"))
      (node (ref "U5") (pin "62") (pinfunction "VDD_7_62") (pintype "power_in"))
      (node (ref "U5") (pin "72") (pinfunction "VDD_1_72") (pintype "power_in"))
      (node (ref "U5") (pin "84") (pinfunction "VDD_8_84") (pintype "power_in"))
      (node (ref "U5") (pin "95") (pinfunction "VDD_9_95") (pintype "power_in"))
      (node (ref "U6") (pin "2") (pinfunction "VCC_2") (pintype "power_in"))
      (node (ref "UEXT") (pin "1") (pinfunction "1_1") (pintype "passive"))
      (node (ref "WKUP") (pin "P$1") (pinfunction "0_P$1") (pintype "passive"))
    )
    (net (code "125") (name "3.3V_A") (class "Default")
      (node (ref "AREF_EN") (pin "1") (pinfunction "1_1") (pintype "passive"))
      (node (ref "C28") (pin "1") (pinfunction "1_1") (pintype "passive"))
      (node (ref "C29") (pin "2") (pinfunction "2_2") (pintype "passive"))
      (node (ref "L4") (pin "2") (pinfunction "2_2") (pintype "passive"))
      (node (ref "U5") (pin "33") (pinfunction "VDDA_33") (pintype "power_in"))
    )
    (net (code "126") (name "AGND") (class "Default")
      (node (ref "AGND_E") (pin "1") (pinfunction "1_1") (pintype "passive"))
      (node (ref "C28") (pin "2") (pinfunction "2_2") (pintype "passive"))
      (node (ref "C29") (pin "1") (pinfunction "1_1") (pintype "passive"))
      (node (ref "C30") (pin "1") (pinfunction "1_1") (pintype "passive"))
      (node (ref "CON4") (pin "7") (pinfunction "7_7") (pintype "passive"))
      (node (ref "U4") (pin "GND@2") (pinfunction "GND_GND@2") (pintype "bidirectional"))
      (node (ref "U5") (pin "31") (pinfunction "VSSA_31") (pintype "power_in"))
    )
    (net (code "127") (name "GND") (class "Default")
      (node (ref "3V_BAT") (pin "2") (pinfunction "2_2") (pintype "passive"))
      (node (ref "AGND_E") (pin "2") (pinfunction "2_2") (pintype "passive"))
      (node (ref "B0_1/B0_0") (pin "3") (pinfunction "3_3") (pintype "passive"))
      (node (ref "B1_1/B1_0") (pin "3") (pinfunction "3_3") (pintype "passive"))
      (node (ref "C1") (pin "2") (pinfunction "2_2") (pintype "passive"))
      (node (ref "C10") (pin "1") (pinfunction "1_1") (pintype "passive"))
      (node (ref "C11") (pin "-") (pinfunction "-_-") (pintype "passive"))
      (node (ref "C12") (pin "2") (pinfunction "2_2") (pintype "passive"))
      (node (ref "C13") (pin "1") (pinfunction "1_1") (pintype "passive"))
      (node (ref "C14") (pin "1") (pinfunction "1_1") (pintype "passive"))
      (node (ref "C15") (pin "1") (pinfunction "1_1") (pintype "passive"))
      (node (ref "C16") (pin "1") (pinfunction "1_1") (pintype "passive"))
      (node (ref "C17") (pin "1") (pinfunction "1_1") (pintype "passive"))
      (node (ref "C18") (pin "1") (pinfunction "1_1") (pintype "passive"))
      (node (ref "C19") (pin "1") (pinfunction "1_1") (pintype "passive"))
      (node (ref "C2") (pin "2") (pinfunction "2_2") (pintype "passive"))
      (node (ref "C20") (pin "1") (pinfunction "1_1") (pintype "passive"))
      (node (ref "C21") (pin "1") (pinfunction "1_1") (pintype "passive"))
      (node (ref "C22") (pin "1") (pinfunction "1_1") (pintype "passive"))
      (node (ref "C23") (pin "1") (pinfunction "1_1") (pintype "passive"))
      (node (ref "C24") (pin "1") (pinfunction "1_1") (pintype "passive"))
      (node (ref "C25") (pin "1") (pinfunction "1_1") (pintype "passive"))
      (node (ref "C26") (pin "1") (pinfunction "1_1") (pintype "passive"))
      (node (ref "C27") (pin "1") (pinfunction "1_1") (pintype "passive"))
      (node (ref "C3") (pin "-") (pinfunction "-_-") (pintype "passive"))
      (node (ref "C31") (pin "2") (pinfunction "2_2") (pintype "passive"))
      (node (ref "C32") (pin "2") (pinfunction "2_2") (pintype "passive"))
      (node (ref "C33") (pin "2") (pinfunction "2_2") (pintype "passive"))
      (node (ref "C34") (pin "2") (pinfunction "2_2") (pintype "passive"))
      (node (ref "C35") (pin "1") (pinfunction "1_1") (pintype "passive"))
      (node (ref "C36") (pin "1") (pinfunction "1_1") (pintype "passive"))
      (node (ref "C39") (pin "2") (pinfunction "2_2") (pintype "passive"))
      (node (ref "C4") (pin "2") (pinfunction "2_2") (pintype "passive"))
      (node (ref "C40") (pin "2") (pinfunction "2_2") (pintype "passive"))
      (node (ref "C41") (pin "2") (pinfunction "2_2") (pintype "passive"))
      (node (ref "C42") (pin "2") (pinfunction "2_2") (pintype "passive"))
      (node (ref "C43") (pin "-") (pinfunction "-_-") (pintype "passive"))
      (node (ref "C44") (pin "-") (pinfunction "-_-") (pintype "passive"))
      (node (ref "C45") (pin "2") (pinfunction "2_2") (pintype "passive"))
      (node (ref "C46") (pin "-") (pinfunction "-_-") (pintype "passive"))
      (node (ref "C47") (pin "2") (pinfunction "2_2") (pintype "passive"))
      (node (ref "C5") (pin "1") (pinfunction "1_1") (pintype "passive"))
      (node (ref "C50") (pin "2") (pinfunction "2_2") (pintype "passive"))
      (node (ref "C51") (pin "2") (pinfunction "2_2") (pintype "passive"))
      (node (ref "C6") (pin "2") (pinfunction "2_2") (pintype "passive"))
      (node (ref "C7") (pin "2") (pinfunction "2_2") (pintype "passive"))
      (node (ref "C8") (pin "2") (pinfunction "2_2") (pintype "passive"))
      (node (ref "C9") (pin "2") (pinfunction "2_2") (pintype "passive"))
      (node (ref "CON1") (pin "4") (pinfunction "4_4") (pintype "passive"))
      (node (ref "CON1") (pin "5") (pinfunction "5_5") (pintype "passive"))
      (node (ref "D1") (pin "3") (pinfunction "3_3") (pintype "passive"))
      (node (ref "D2") (pin "3") (pinfunction "3_3") (pintype "passive"))
      (node (ref "D4") (pin "A") (pinfunction "1_A") (pintype "passive"))
      (node (ref "FET1") (pin "1") (pinfunction "G_1") (pintype "passive"))
      (node (ref "GND_PIN") (pin "P$1") (pinfunction "PP_P$1") (pintype "passive"))
      (node (ref "JTAG") (pin "10") (pinfunction "10_10") (pintype "passive"))
      (node (ref "JTAG") (pin "12") (pinfunction "12_12") (pintype "passive"))
      (node (ref "JTAG") (pin "14") (pinfunction "14_14") (pintype "passive"))
      (node (ref "JTAG") (pin "16") (pinfunction "16_16") (pintype "passive"))
      (node (ref "JTAG") (pin "18") (pinfunction "18_18") (pintype "passive"))
      (node (ref "JTAG") (pin "20") (pinfunction "20_20") (pintype "passive"))
      (node (ref "JTAG") (pin "4") (pinfunction "4_4") (pintype "passive"))
      (node (ref "JTAG") (pin "6") (pinfunction "6_6") (pintype "passive"))
      (node (ref "JTAG") (pin "8") (pinfunction "8_8") (pintype "passive"))
      (node (ref "L2") (pin "1") (pinfunction "1_1") (pintype "passive"))
      (node (ref "L3") (pin "1") (pinfunction "1_1") (pintype "passive"))
      (node (ref "PD") (pin "2") (pinfunction "2_2") (pintype "passive"))
      (node (ref "PD") (pin "20") (pinfunction "20_20") (pintype "passive"))
      (node (ref "PE") (pin "2") (pinfunction "2_2") (pintype "passive"))
      (node (ref "PE") (pin "20") (pinfunction "20_20") (pintype "passive"))
      (node (ref "PF") (pin "2") (pinfunction "2_2") (pintype "passive"))
      (node (ref "PF") (pin "20") (pinfunction "20_20") (pintype "passive"))
      (node (ref "PG") (pin "2") (pinfunction "2_2") (pintype "passive"))
      (node (ref "PG") (pin "20") (pinfunction "20_20") (pintype "passive"))
      (node (ref "PWR_JACK") (pin "-") (pinfunction "-_-") (pintype "passive"))
      (node (ref "PWR_JACK") (pin "--") (pinfunction "--_--") (pintype "passive"))
      (node (ref "PWR_LED") (pin "C") (pinfunction "C_C") (pintype "passive"))
      (node (ref "Q2") (pin "GND") (pinfunction "GND_GND") (pintype "bidirectional"))
      (node (ref "R14") (pin "2") (pinfunction "2_2") (pintype "passive"))
      (node (ref "R37") (pin "1") (pinfunction "1_1") (pintype "passive"))
      (node (ref "R38") (pin "2") (pinfunction "2_2") (pintype "passive"))
      (node (ref "R40") (pin "2") (pinfunction "2_2") (pintype "passive"))
      (node (ref "R41") (pin "2") (pinfunction "2_2") (pintype "passive"))
      (node (ref "R7") (pin "2") (pinfunction "2_2") (pintype "passive"))
      (node (ref "RESET") (pin "P$2") (pinfunction "1_P$2") (pintype "passive"))
      (node (ref "RM2") (pin "2.1") (pinfunction "1_2.1") (pintype "passive"))
      (node (ref "RM3") (pin "1.2") (pinfunction "2_1.2") (pintype "passive"))
      (node (ref "RM3") (pin "2.2") (pinfunction "2_2.2") (pintype "passive"))
      (node (ref "RM3") (pin "3.2") (pinfunction "2_3.2") (pintype "passive"))
      (node (ref "RM4") (pin "1.2") (pinfunction "2_1.2") (pintype "passive"))
      (node (ref "RM4") (pin "4.2") (pinfunction "2_4.2") (pintype "passive"))
      (node (ref "SD/MMC") (pin "6") (pinfunction "VSS_6") (pintype "power_in"))
      (node (ref "U1") (pin "2") (pinfunction "2_2") (pintype "power_in"))
      (node (ref "U2") (pin "6") (pinfunction "GND_6") (pintype "power_in"))
      (node (ref "U3") (pin "2") (pinfunction "2_2") (pintype "power_in"))
      (node (ref "U3BOOT") (pin "3") (pinfunction "3_3") (pintype "passive"))
      (node (ref "U4") (pin "GND") (pinfunction "GND_GND") (pintype "bidirectional"))
      (node (ref "U4") (pin "GND@1") (pinfunction "GND_GND@1") (pintype "bidirectional"))
      (node (ref "U5") (pin "107") (pinfunction "VSS_2_107") (pintype "power_in"))
      (node (ref "U5") (pin "120") (pinfunction "VSS_10_120") (pintype "power_in"))
      (node (ref "U5") (pin "130") (pinfunction "VSS_11_130") (pintype "power_in"))
      (node (ref "U5") (pin "16") (pinfunction "VSS_5_16") (pintype "power_in"))
      (node (ref "U5") (pin "38") (pinfunction "VSS_4_38") (pintype "power_in"))
      (node (ref "U5") (pin "51") (pinfunction "VSS_6_51") (pintype "power_in"))
      (node (ref "U5") (pin "61") (pinfunction "VSS_7_61") (pintype "power_in"))
      (node (ref "U5") (pin "83") (pinfunction "VSS_8_83") (pintype "power_in"))
      (node (ref "U5") (pin "94") (pinfunction "VSS_9_94") (pintype "power_in"))
      (node (ref "U6") (pin "3") (pinfunction "GND_3") (pintype "power_in"))
      (node (ref "U7") (pin "2") (pinfunction "GND_2") (pintype "bidirectional"))
      (node (ref "U8") (pin "4") (pinfunction "GND_4") (pintype "bidirectional"))
      (node (ref "UEXT") (pin "2") (pinfunction "2_2") (pintype "passive"))
      (node (ref "USB_HOST") (pin "4") (pinfunction "4_4") (pintype "passive"))
      (node (ref "USB_OTG") (pin "GND") (pinfunction "GND_GND") (pintype "power_in"))
    )
    (net (code "128") (name "Net-(3.3V_E-Pad1)") (class "Default")
      (node (ref "3.3V_E") (pin "1") (pinfunction "1_1") (pintype "passive"))
      (node (ref "C38") (pin "1") (pinfunction "1_1") (pintype "passive"))
      (node (ref "C40") (pin "1") (pinfunction "1_1") (pintype "passive"))
      (node (ref "C41") (pin "1") (pinfunction "1_1") (pintype "passive"))
      (node (ref "C42") (pin "1") (pinfunction "1_1") (pintype "passive"))
      (node (ref "C44") (pin "+") (pinfunction "+_+") (pintype "passive"))
      (node (ref "L6") (pin "2") (pinfunction "2_2") (pintype "passive"))
      (node (ref "R33") (pin "1") (pinfunction "1_1") (pintype "passive"))
    )
    (net (code "129") (name "Net-(B0_1/B0_0-Pad2)") (class "Default")
      (node (ref "B0_1/B0_0") (pin "2") (pinfunction "2_2") (pintype "passive"))
      (node (ref "R17") (pin "2") (pinfunction "2_2") (pintype "passive"))
    )
    (net (code "130") (name "Net-(B1_1/B1_0-Pad2)") (class "Default")
      (node (ref "B1_1/B1_0") (pin "2") (pinfunction "2_2") (pintype "passive"))
      (node (ref "R15") (pin "2") (pinfunction "2_2") (pintype "passive"))
    )
    (net (code "131") (name "Net-(C32-Pad1)") (class "Default")
      (node (ref "C32") (pin "1") (pinfunction "1_1") (pintype "passive"))
      (node (ref "Q1") (pin "1") (pinfunction "1_1") (pintype "passive"))
      (node (ref "R20") (pin "1") (pinfunction "1_1") (pintype "passive"))
    )
    (net (code "132") (name "Net-(C49-Pad2)") (class "Default")
      (node (ref "C49") (pin "2") (pinfunction "2_2") (pintype "passive"))
      (node (ref "R40") (pin "1") (pinfunction "1_1") (pintype "passive"))
    )
    (net (code "133") (name "Net-(D3-A2)") (class "Default")
      (node (ref "3V_BAT") (pin "1") (pinfunction "1_1") (pintype "passive"))
      (node (ref "D3") (pin "2") (pinfunction "A2_2") (pintype "passive"))
    )
    (net (code "134") (name "Net-(FET1-D)") (class "Default")
      (node (ref "FET1") (pin "3") (pinfunction "D_3") (pintype "passive"))
      (node (ref "PWR_JACK") (pin "+") (pinfunction "+_+") (pintype "passive"))
    )
    (net (code "135") (name "Net-(L3-Pad2)") (class "Default")
      (node (ref "L3") (pin "2") (pinfunction "2_2") (pintype "passive"))
      (node (ref "USB_OTG") (pin "GND1") (pinfunction "GND1_GND1") (pintype "input"))
      (node (ref "USB_OTG") (pin "GND2") (pinfunction "GND2_GND2") (pintype "input"))
      (node (ref "USB_OTG") (pin "GND3") (pinfunction "GND3_GND3") (pintype "input"))
      (node (ref "USB_OTG") (pin "GND4") (pinfunction "GND4_GND4") (pintype "input"))
    )
    (net (code "136") (name "Net-(LED-PadA)") (class "Default")
      (node (ref "LED") (pin "A") (pinfunction "A_A") (pintype "passive"))
      (node (ref "R35") (pin "1") (pinfunction "1_1") (pintype "passive"))
    )
    (net (code "137") (name "Net-(PD-Pad5)") (class "Default")
      (node (ref "PD") (pin "5") (pinfunction "5_5") (pintype "passive"))
      (node (ref "R23") (pin "2") (pinfunction "2_2") (pintype "passive"))
    )
    (net (code "138") (name "Net-(PG-Pad10)") (class "Default")
      (node (ref "PG") (pin "10") (pinfunction "10_10") (pintype "passive"))
      (node (ref "R24") (pin "2") (pinfunction "2_2") (pintype "passive"))
    )
    (net (code "139") (name "Net-(PG-Pad11)") (class "Default")
      (node (ref "PG") (pin "11") (pinfunction "11_11") (pintype "passive"))
      (node (ref "R25") (pin "1") (pinfunction "1_1") (pintype "passive"))
    )
    (net (code "140") (name "Net-(PG-Pad15)") (class "Default")
      (node (ref "PG") (pin "15") (pinfunction "15_15") (pintype "passive"))
      (node (ref "R26") (pin "1") (pinfunction "1_1") (pintype "passive"))
    )
    (net (code "141") (name "Net-(PG-Pad16)") (class "Default")
      (node (ref "PG") (pin "16") (pinfunction "16_16") (pintype "passive"))
      (node (ref "R27") (pin "2") (pinfunction "2_2") (pintype "passive"))
    )
    (net (code "142") (name "Net-(PG-Pad17)") (class "Default")
      (node (ref "PG") (pin "17") (pinfunction "17_17") (pintype "passive"))
      (node (ref "R28") (pin "1") (pinfunction "1_1") (pintype "passive"))
    )
    (net (code "143") (name "Net-(PG-Pad18)") (class "Default")
      (node (ref "PG") (pin "18") (pinfunction "18_18") (pintype "passive"))
      (node (ref "R29") (pin "2") (pinfunction "2_2") (pintype "passive"))
    )
    (net (code "144") (name "Net-(PWR_LED-PadA)") (class "Default")
      (node (ref "PWR_LED") (pin "A") (pinfunction "A_A") (pintype "passive"))
      (node (ref "R34") (pin "2") (pinfunction "2_2") (pintype "passive"))
    )
    (net (code "145") (name "Net-(R2-Pad2)") (class "Default")
      (node (ref "R2") (pin "2") (pinfunction "2_2") (pintype "passive"))
      (node (ref "U1") (pin "6") (pinfunction "6_6") (pintype "bidirectional"))
    )
    (net (code "146") (name "Net-(R4-Pad2)") (class "Default")
      (node (ref "R4") (pin "2") (pinfunction "2_2") (pintype "passive"))
      (node (ref "U1") (pin "4") (pinfunction "4_4") (pintype "bidirectional"))
    )
    (net (code "147") (name "Net-(R9-Pad2)") (class "Default")
      (node (ref "R9") (pin "2") (pinfunction "2_2") (pintype "passive"))
      (node (ref "U3") (pin "4") (pinfunction "4_4") (pintype "bidirectional"))
    )
    (net (code "148") (name "Net-(R10-Pad2)") (class "Default")
      (node (ref "R10") (pin "2") (pinfunction "2_2") (pintype "passive"))
      (node (ref "U3") (pin "6") (pinfunction "6_6") (pintype "bidirectional"))
    )
    (net (code "149") (name "Net-(R11-1.1)") (class "Default")
      (node (ref "C16") (pin "2") (pinfunction "2_2") (pintype "passive"))
      (node (ref "R11") (pin "1") (pinfunction "1.1_1") (pintype "passive"))
      (node (ref "R14") (pin "1") (pinfunction "1_1") (pintype "passive"))
      (node (ref "U5") (pin "143") (pinfunction "VDD_3_143") (pintype "power_in"))
    )
    (net (code "150") (name "Net-(RESET-0)") (class "Default")
      (node (ref "C35") (pin "2") (pinfunction "2_2") (pintype "passive"))
      (node (ref "R19") (pin "1") (pinfunction "1_1") (pintype "passive"))
      (node (ref "R21") (pin "2") (pinfunction "2_2") (pintype "passive"))
      (node (ref "RESET") (pin "P$1") (pinfunction "0_P$1") (pintype "passive"))
      (node (ref "U6") (pin "1") (pinfunction "RESET_1") (pintype "output"))
    )
    (net (code "151") (name "Net-(RM3B-1)") (class "Default")
      (node (ref "JTAG") (pin "17") (pinfunction "17_17") (pintype "passive"))
      (node (ref "RM3") (pin "2.1") (pinfunction "1_2.1") (pintype "passive"))
    )
    (net (code "152") (name "Net-(RM3C-1)") (class "Default")
      (node (ref "JTAG") (pin "11") (pinfunction "11_11") (pintype "passive"))
      (node (ref "R5") (pin "1") (pinfunction "1_1") (pintype "passive"))
      (node (ref "RM3") (pin "3.1") (pinfunction "1_3.1") (pintype "passive"))
    )
    (net (code "153") (name "Net-(SD/MMC-VDD)") (class "Default")
      (node (ref "C45") (pin "1") (pinfunction "1_1") (pintype "passive"))
      (node (ref "C7") (pin "1") (pinfunction "1_1") (pintype "passive"))
      (node (ref "L1") (pin "2") (pinfunction "2_2") (pintype "passive"))
      (node (ref "SD/MMC") (pin "4") (pinfunction "VDD_4") (pintype "power_in"))
    )
    (net (code "154") (name "Net-(U5-PC14{slash}OSC32_IN)") (class "Default")
      (node (ref "C33") (pin "1") (pinfunction "1_1") (pintype "passive"))
      (node (ref "Q2") (pin "2") (pinfunction "2_2") (pintype "passive"))
      (node (ref "R22") (pin "2") (pinfunction "2_2") (pintype "passive"))
      (node (ref "U5") (pin "8") (pinfunction "PC14/OSC32_IN_8") (pintype "bidirectional"))
    )
    (net (code "155") (name "Net-(U5-PC15{slash}OSC32_OUT)") (class "Default")
      (node (ref "C34") (pin "1") (pinfunction "1_1") (pintype "passive"))
      (node (ref "Q2") (pin "1") (pinfunction "1_1") (pintype "passive"))
      (node (ref "R22") (pin "1") (pinfunction "1_1") (pintype "passive"))
      (node (ref "U5") (pin "9") (pinfunction "PC15/OSC32_OUT_9") (pintype "bidirectional"))
    )
    (net (code "156") (name "Net-(U5-PH0{slash}OSC_IN)") (class "Default")
      (node (ref "C31") (pin "1") (pinfunction "1_1") (pintype "passive"))
      (node (ref "Q1") (pin "2") (pinfunction "2_2") (pintype "passive"))
      (node (ref "R18") (pin "2") (pinfunction "2_2") (pintype "passive"))
      (node (ref "U5") (pin "23") (pinfunction "PH0/OSC_IN_23") (pintype "input"))
    )
    (net (code "157") (name "Net-(U5-PH1{slash}OSC_OUT)") (class "Default")
      (node (ref "R18") (pin "1") (pinfunction "1_1") (pintype "passive"))
      (node (ref "R20") (pin "2") (pinfunction "2_2") (pintype "passive"))
      (node (ref "U5") (pin "24") (pinfunction "PH1/OSC_OUT_24") (pintype "output"))
    )
    (net (code "158") (name "Net-(U5-VCAP_1)") (class "Default")
      (node (ref "C13") (pin "2") (pinfunction "2_2") (pintype "passive"))
      (node (ref "U5") (pin "71") (pinfunction "VCAP_1_71") (pintype "output"))
    )
    (net (code "159") (name "Net-(U5-VCAP_2)") (class "Default")
      (node (ref "C27") (pin "2") (pinfunction "2_2") (pintype "passive"))
      (node (ref "U5") (pin "106") (pinfunction "VCAP_2_106") (pintype "output"))
    )
    (net (code "160") (name "Net-(U5-VREF+)") (class "Default")
      (node (ref "C30") (pin "2") (pinfunction "2_2") (pintype "passive"))
      (node (ref "R16") (pin "2") (pinfunction "2_2") (pintype "passive"))
      (node (ref "U5") (pin "32") (pinfunction "VREF+_32") (pintype "power_in"))
    )
    (net (code "161") (name "Net-(U7-FB)") (class "Default")
      (node (ref "C38") (pin "2") (pinfunction "2_2") (pintype "passive"))
      (node (ref "R33") (pin "2") (pinfunction "2_2") (pintype "passive"))
      (node (ref "R38") (pin "1") (pinfunction "1_1") (pintype "passive"))
      (node (ref "U7") (pin "5") (pinfunction "FB_5") (pintype "bidirectional"))
    )
    (net (code "162") (name "Net-(U7-LX)") (class "Default")
      (node (ref "L6") (pin "1") (pinfunction "1_1") (pintype "passive"))
      (node (ref "U7") (pin "3") (pinfunction "LX_3") (pintype "bidirectional"))
    )
    (net (code "163") (name "Net-(U8-BS)") (class "Default")
      (node (ref "C48") (pin "1") (pinfunction "1_1") (pintype "passive"))
      (node (ref "U8") (pin "1") (pinfunction "BS_1") (pintype "bidirectional"))
    )
    (net (code "164") (name "Net-(U8-COMP)") (class "Default")
      (node (ref "C49") (pin "1") (pinfunction "1_1") (pintype "passive"))
      (node (ref "U8") (pin "6") (pinfunction "COMP_6") (pintype "bidirectional"))
    )
    (net (code "165") (name "Net-(U8-EN)") (class "Default")
      (node (ref "R39") (pin "2") (pinfunction "2_2") (pintype "passive"))
      (node (ref "U8") (pin "7") (pinfunction "EN_7") (pintype "bidirectional"))
    )
    (net (code "166") (name "Net-(U8-FB)") (class "Default")
      (node (ref "R41") (pin "1") (pinfunction "1_1") (pintype "passive"))
      (node (ref "R42") (pin "1") (pinfunction "1_1") (pintype "passive"))
      (node (ref "U8") (pin "5") (pinfunction "FB_5") (pintype "bidirectional"))
    )
    (net (code "167") (name "Net-(U8-SS)") (class "Default")
      (node (ref "C47") (pin "1") (pinfunction "1_1") (pintype "passive"))
      (node (ref "U8") (pin "8") (pinfunction "SS_8") (pintype "bidirectional"))
    )
    (net (code "168") (name "Net-(U8-SW)") (class "Default")
      (node (ref "C48") (pin "2") (pinfunction "2_2") (pintype "passive"))
      (node (ref "L5") (pin "1") (pinfunction "1_1") (pintype "passive"))
      (node (ref "U8") (pin "3") (pinfunction "SW_3") (pintype "bidirectional"))
    )
    (net (code "169") (name "Net-(USB_HOST-5)") (class "Default")
      (node (ref "L2") (pin "2") (pinfunction "2_2") (pintype "passive"))
      (node (ref "USB_HOST") (pin "P$3") (pinfunction "5_P$3") (pintype "input"))
      (node (ref "USB_HOST") (pin "P$4") (pinfunction "6_P$4") (pintype "input"))
    )
    (net (code "170") (name "Net-(WKUP-1)") (class "Default")
      (node (ref "C37") (pin "1") (pinfunction "1_1") (pintype "passive"))
      (node (ref "R36") (pin "1") (pinfunction "1_1") (pintype "passive"))
      (node (ref "R37") (pin "2") (pinfunction "2_2") (pintype "passive"))
      (node (ref "WKUP") (pin "P$2") (pinfunction "1_P$2") (pintype "passive"))
    )
    (net (code "171") (name "VIN") (class "Default")
      (node (ref "C46") (pin "+") (pinfunction "+_+") (pintype "passive"))
      (node (ref "CON1") (pin "6") (pinfunction "6_6") (pintype "passive"))
      (node (ref "D4") (pin "C") (pinfunction "2_C") (pintype "passive"))
      (node (ref "FET1") (pin "2") (pinfunction "S_2") (pintype "passive"))
      (node (ref "R39") (pin "1") (pinfunction "1_1") (pintype "passive"))
      (node (ref "U4") (pin "VIN") (pinfunction "VIN_VIN") (pintype "bidirectional"))
      (node (ref "U8") (pin "2") (pinfunction "IN_2") (pintype "bidirectional"))
    )
  )
)
